# SOM_EVAL_BOARD_V101.net
KiCad netlist of a schematic drawn in EAGLE
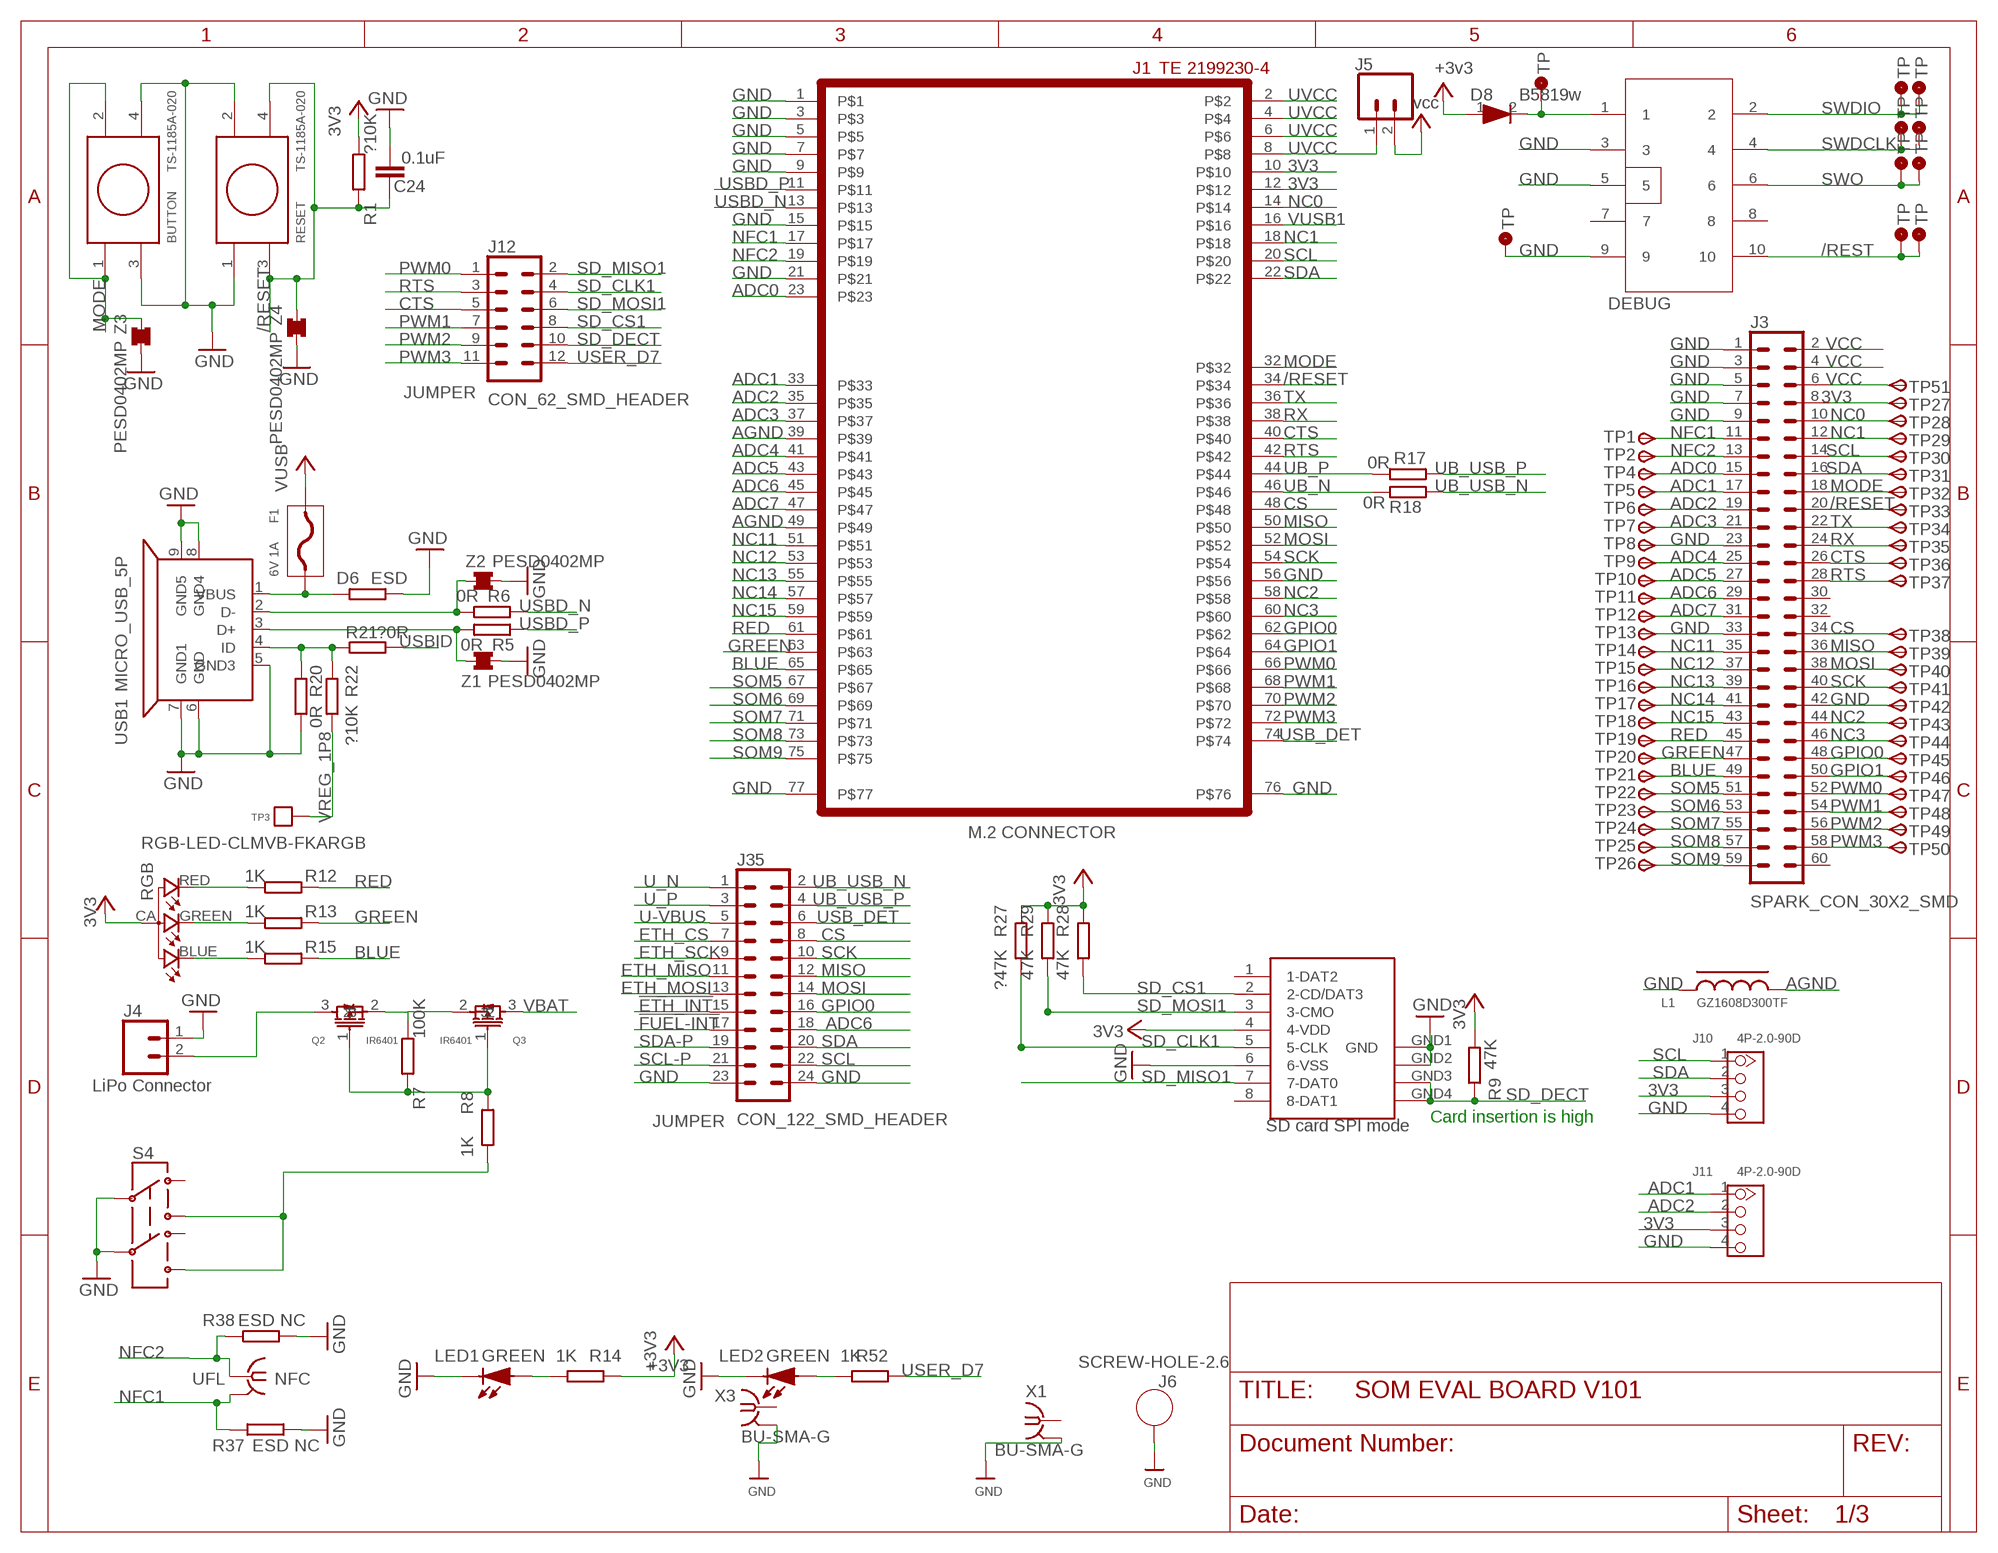
[diagram p0: schematic, sheet 1]
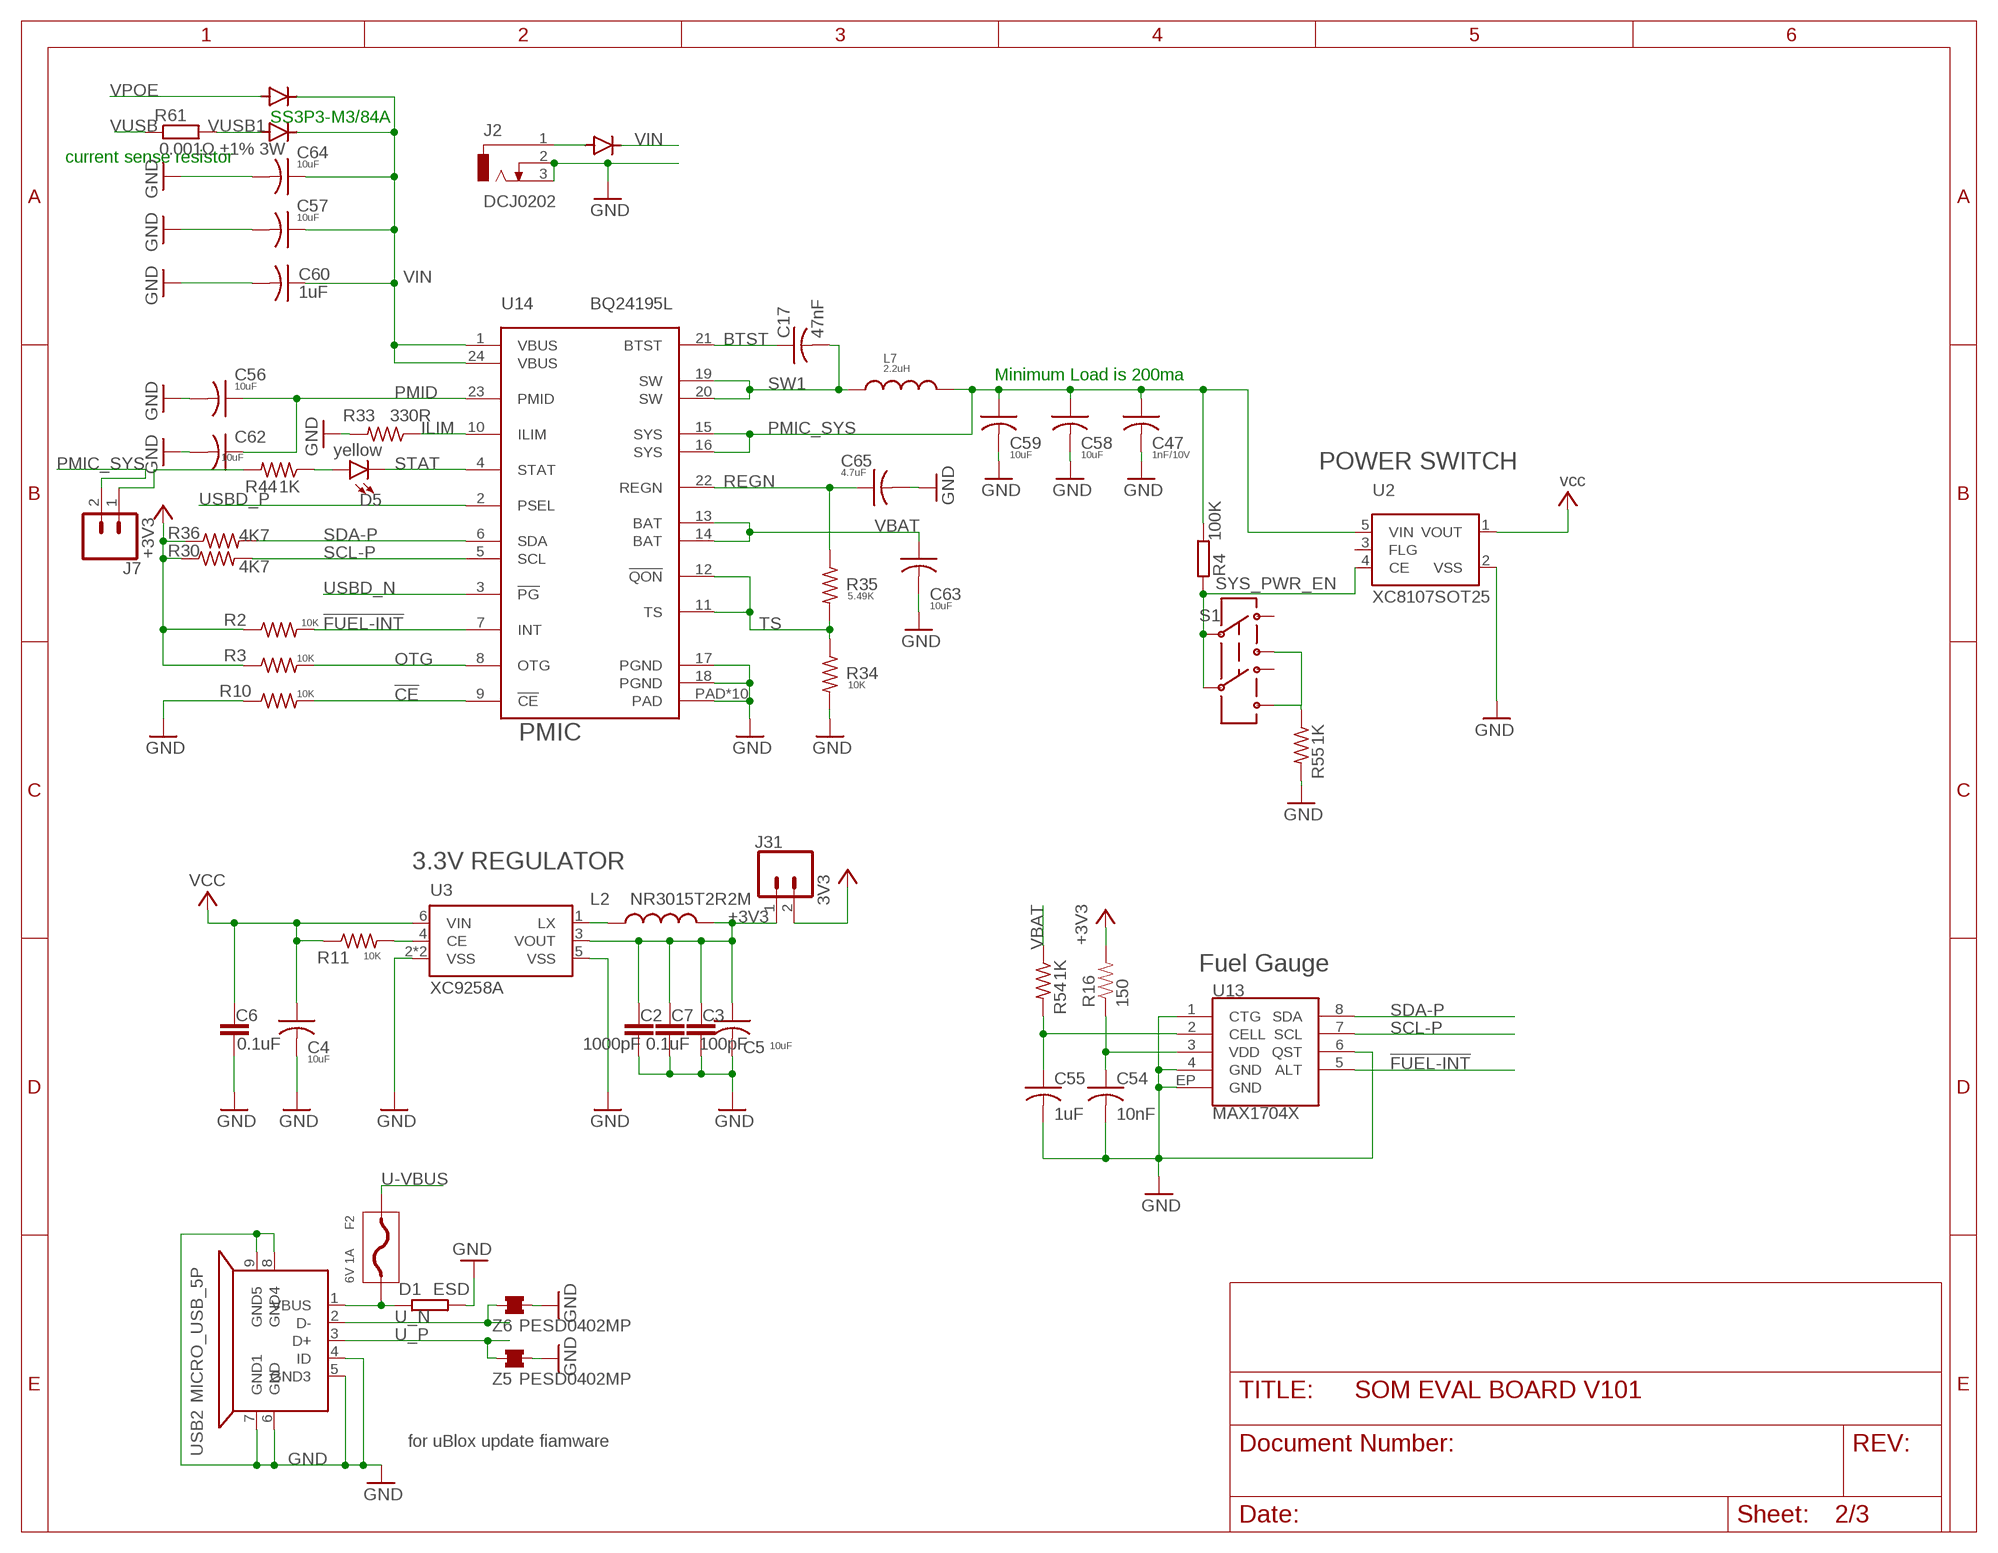
[diagram p1: schematic, sheet 2]
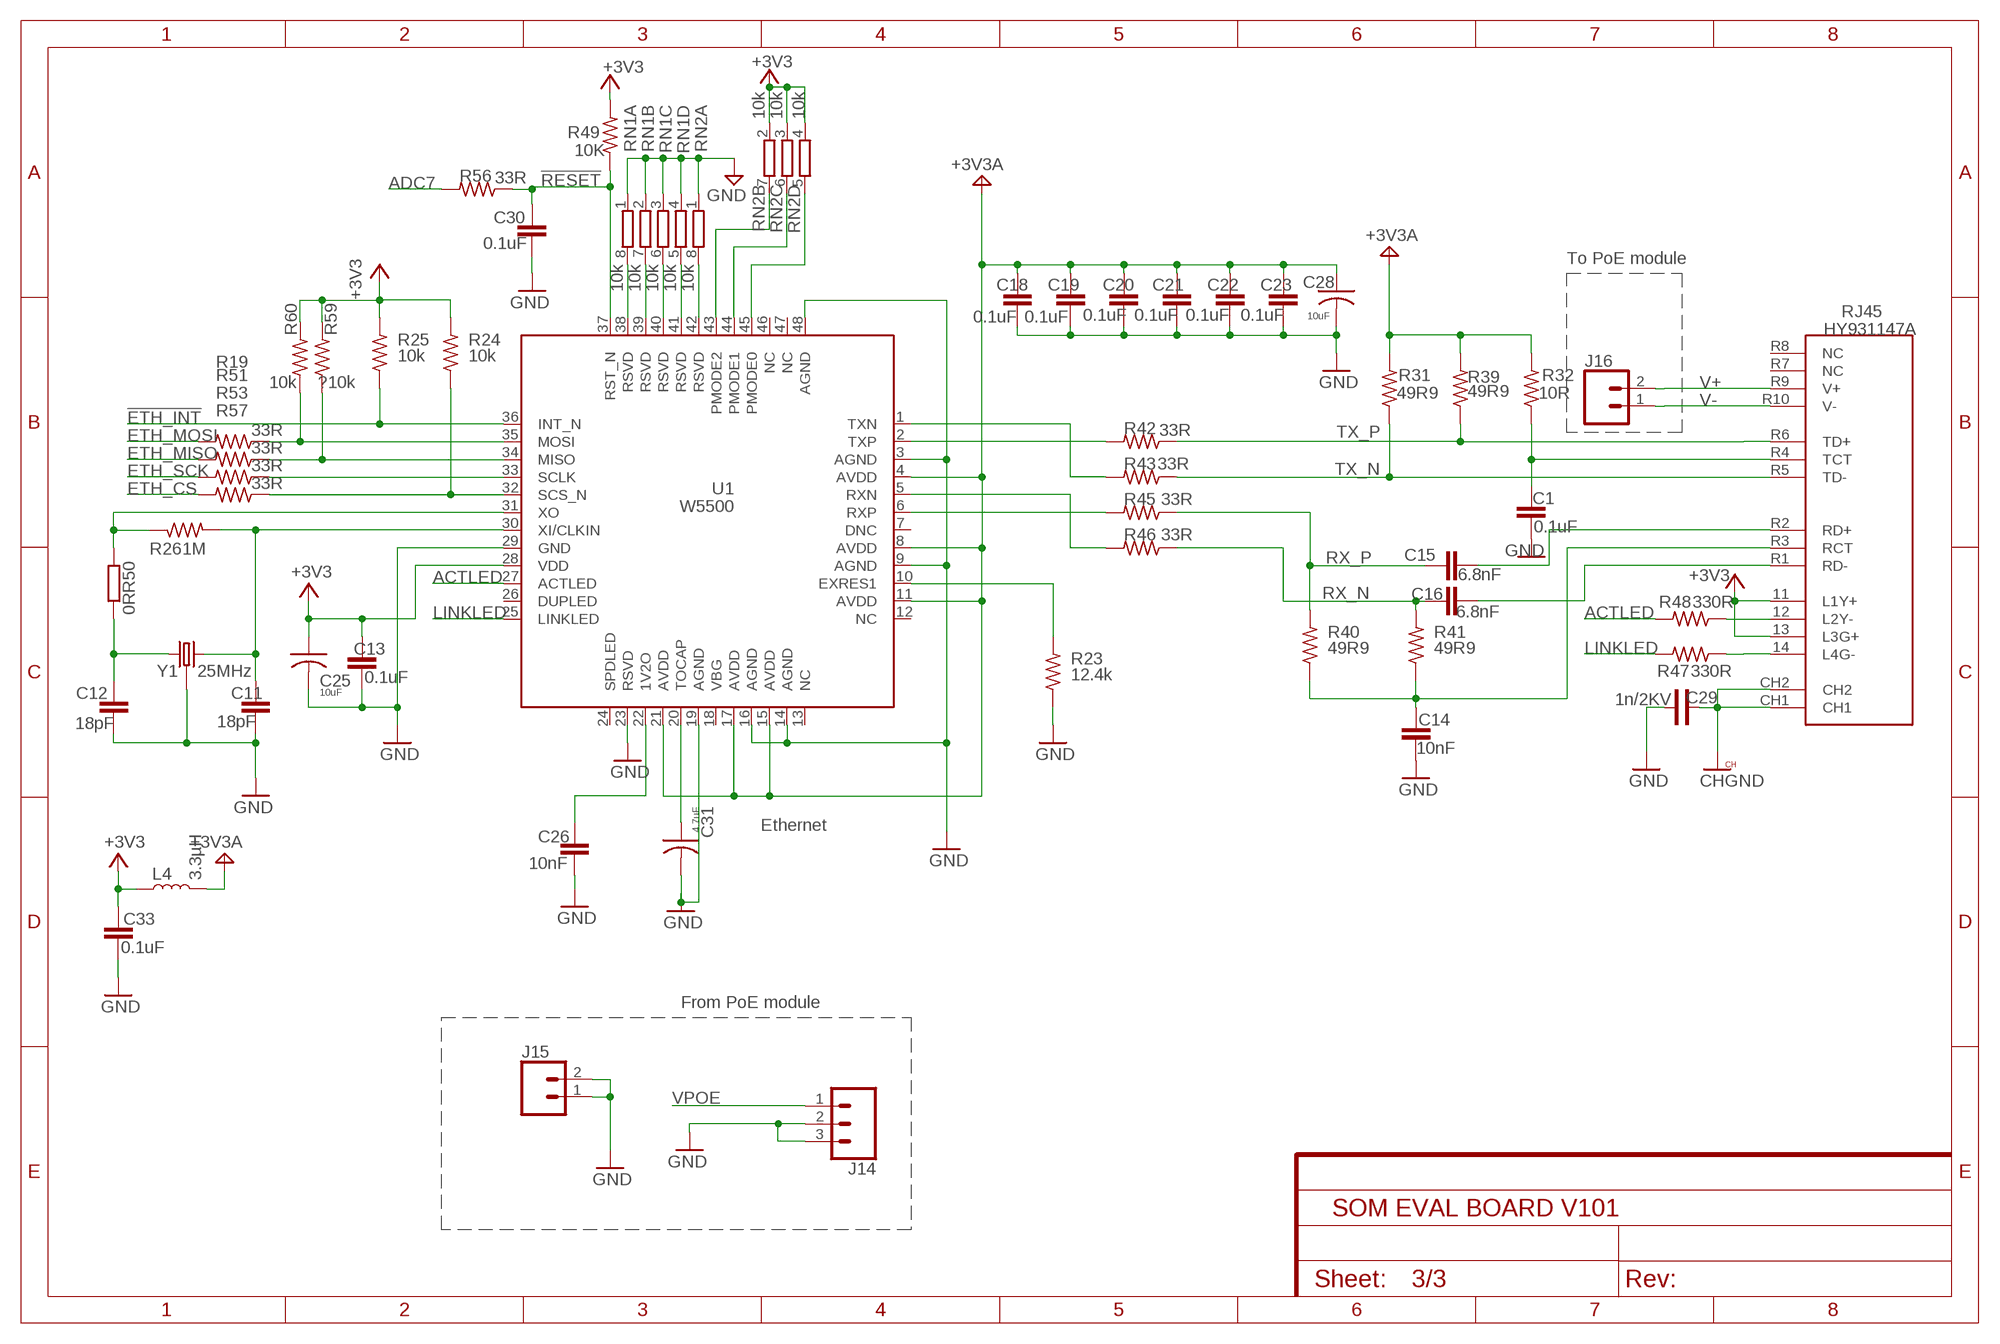
[diagram p2: schematic, sheet 3]

(export (version "E")
  (design (tool "Eeschema 10.0.6"))
  (components
    (comp (ref "BUTTON")
      (value "TS-1185A-020")
      (footprint "eagle-import:TS-1185A-020")
      (libsource (lib "eagle-import") (part "TS-1185A-020"))
    )
    (comp (ref "C24")
      (value "0.1uF")
      (footprint "eagle-import:C0402_B")
      (libsource (lib "eagle-import") (part "CAP_1"))
    )
    (comp (ref "D6")
      (value "ESD")
      (footprint "eagle-import:R-0402S")
      (libsource (lib "eagle-import") (part "RES0402S"))
    )
    (comp (ref "D8")
      (value "B5819w")
      (footprint "eagle-import:SOD-123")
      (libsource (lib "eagle-import") (part "DIODESOD123"))
    )
    (comp (ref "DEBUG")
      (value "CON5X2")
      (footprint "eagle-import:CON5X2_1.27")
      (libsource (lib "eagle-import") (part "CON5X2"))
    )
    (comp (ref "F1")
      (value "6V 1A")
      (footprint "eagle-import:F0805")
      (libsource (lib "eagle-import") (part "FUSE"))
    )
    (comp (ref "J1")
      (value "TE 2199230-4")
      (footprint "eagle-import:M.2EKEY")
      (libsource (lib "eagle-import") (part "M.2EKEY"))
    )
    (comp (ref "J3")
      (value "SPARK_CON_30X2_SMD")
      (footprint "eagle-import:SPARK_CON_30X2_SMD")
      (libsource (lib "eagle-import") (part "SPARK_CON_30X2_SMD"))
    )
    (comp (ref "J4")
      (value "CONN_02-JST-2MM-SMT")
      (footprint "eagle-import:JST-2-SMD")
      (libsource (lib "eagle-import") (part "CONN_02-JST-2MM-SMT"))
    )
    (comp (ref "J5")
      (value "CONN_02")
      (footprint "eagle-import:1X02")
      (libsource (lib "eagle-import") (part "SparkFun-Connectors_513_CONN_02"))
    )
    (comp (ref "J6")
      (value "SCREW-HOLE-2.6")
      (footprint "eagle-import:SCREW-HOLE-2.6")
      (libsource (lib "eagle-import") (part "SCREW-HOLE-2.6"))
    )
    (comp (ref "J10")
      (value "4P-2.0-90D")
      (footprint "eagle-import:HW4-2.0-90D")
      (libsource (lib "eagle-import") (part "GROVE-CONNECTOR-DIP-90D(4P-2.0)"))
    )
    (comp (ref "J11")
      (value "4P-2.0-90D")
      (footprint "eagle-import:HW4-2.0-90D")
      (libsource (lib "eagle-import") (part "GROVE-CONNECTOR-DIP-90D(4P-2.0)"))
    )
    (comp (ref "J12")
      (value "CON_62_SMD_HEADER")
      (footprint "eagle-import:CON_6_2_SMD_HEADER")
      (libsource (lib "eagle-import") (part "CON_62_SMD_HEADER"))
    )
    (comp (ref "J35")
      (value "CON_122_SMD_HEADER")
      (footprint "eagle-import:CON_12_2_SMD_HEADER")
      (libsource (lib "eagle-import") (part "CON_122_SMD_HEADER"))
    )
    (comp (ref "L1")
      (value "GZ1608D300TF")
      (footprint "eagle-import:R-0603A")
      (libsource (lib "eagle-import") (part "L"))
    )
    (comp (ref "LED1")
      (value "GREEN")
      (footprint "eagle-import:LED0603")
      (libsource (lib "eagle-import") (part "LED"))
    )
    (comp (ref "LED2")
      (value "GREEN")
      (footprint "eagle-import:LED0603")
      (libsource (lib "eagle-import") (part "LED"))
    )
    (comp (ref "NFC")
      (value "UFL")
      (footprint "eagle-import:IPEX-20279-001E")
      (libsource (lib "eagle-import") (part "IPEX-20279-001E"))
    )
    (comp (ref "P1")
      (value "SPARK_POGOPIN")
      (footprint "eagle-import:SPARK_POGO-2.0")
      (libsource (lib "eagle-import") (part "SPARK_POGOPIN"))
    )
    (comp (ref "P2")
      (value "SPARK_POGOPIN")
      (footprint "eagle-import:SPARK_POGO-2.0")
      (libsource (lib "eagle-import") (part "SPARK_POGOPIN"))
    )
    (comp (ref "P3")
      (value "SPARK_POGOPIN")
      (footprint "eagle-import:SPARK_POGO-2.0")
      (libsource (lib "eagle-import") (part "SPARK_POGOPIN"))
    )
    (comp (ref "P4")
      (value "SPARK_POGOPIN")
      (footprint "eagle-import:SPARK_POGO-2.0")
      (libsource (lib "eagle-import") (part "SPARK_POGOPIN"))
    )
    (comp (ref "Q2")
      (value "IR6401")
      (footprint "eagle-import:SOT-23")
      (libsource (lib "eagle-import") (part "PMOS"))
    )
    (comp (ref "Q3")
      (value "IR6401")
      (footprint "eagle-import:SOT-23")
      (libsource (lib "eagle-import") (part "PMOS"))
    )
    (comp (ref "R1")
      (value "?10K")
      (footprint "eagle-import:R-0402S")
      (libsource (lib "eagle-import") (part "RES0402S"))
    )
    (comp (ref "R5")
      (value "0R")
      (footprint "eagle-import:R-0402S")
      (libsource (lib "eagle-import") (part "RES0402S"))
    )
    (comp (ref "R6")
      (value "0R")
      (footprint "eagle-import:R-0402S")
      (libsource (lib "eagle-import") (part "RES0402S"))
    )
    (comp (ref "R7")
      (value "100K")
      (footprint "eagle-import:R0603")
      (libsource (lib "eagle-import") (part "RESR0603"))
    )
    (comp (ref "R8")
      (value "1K")
      (footprint "eagle-import:R-0402S")
      (libsource (lib "eagle-import") (part "RES0402S"))
    )
    (comp (ref "R9")
      (value "47K")
      (footprint "eagle-import:R-0402S")
      (libsource (lib "eagle-import") (part "RES0402S"))
    )
    (comp (ref "R12")
      (value "1K")
      (footprint "eagle-import:R-0402S")
      (libsource (lib "eagle-import") (part "RES0402S"))
    )
    (comp (ref "R13")
      (value "1K")
      (footprint "eagle-import:R-0402S")
      (libsource (lib "eagle-import") (part "RES0402S"))
    )
    (comp (ref "R14")
      (value "1K")
      (footprint "eagle-import:R-0402S")
      (libsource (lib "eagle-import") (part "RES0402S"))
    )
    (comp (ref "R15")
      (value "1K")
      (footprint "eagle-import:R-0402S")
      (libsource (lib "eagle-import") (part "RES0402S"))
    )
    (comp (ref "R17")
      (value "0R")
      (footprint "eagle-import:R-0402S")
      (libsource (lib "eagle-import") (part "RES0402S"))
    )
    (comp (ref "R18")
      (value "0R")
      (footprint "eagle-import:R-0402S")
      (libsource (lib "eagle-import") (part "RES0402S"))
    )
    (comp (ref "R20")
      (value "0R")
      (footprint "eagle-import:R-0402S")
      (libsource (lib "eagle-import") (part "RES0402S"))
    )
    (comp (ref "R21")
      (value "?0R")
      (footprint "eagle-import:R-0402S")
      (libsource (lib "eagle-import") (part "RES0402S"))
    )
    (comp (ref "R22")
      (value "?10K")
      (footprint "eagle-import:R-0402S")
      (libsource (lib "eagle-import") (part "RES0402S"))
    )
    (comp (ref "R27")
      (value "?47K")
      (footprint "eagle-import:R-0402S")
      (libsource (lib "eagle-import") (part "RES0402S"))
    )
    (comp (ref "R28")
      (value "47K")
      (footprint "eagle-import:R-0402S")
      (libsource (lib "eagle-import") (part "RES0402S"))
    )
    (comp (ref "R29")
      (value "47K")
      (footprint "eagle-import:R-0402S")
      (libsource (lib "eagle-import") (part "RES0402S"))
    )
    (comp (ref "R37")
      (value "ESD NC")
      (footprint "eagle-import:R-0402S")
      (libsource (lib "eagle-import") (part "RES0402S"))
    )
    (comp (ref "R38")
      (value "ESD NC")
      (footprint "eagle-import:R-0402S")
      (libsource (lib "eagle-import") (part "RES0402S"))
    )
    (comp (ref "R52")
      (value "1K")
      (footprint "eagle-import:R-0402S")
      (libsource (lib "eagle-import") (part "RES0402S"))
    )
    (comp (ref "RESET")
      (value "TS-1185A-020")
      (footprint "eagle-import:TS-1185A-020")
      (libsource (lib "eagle-import") (part "TS-1185A-020"))
    )
    (comp (ref "RGB")
      (value "RGB-LED-CLMVB-FKARGB")
      (footprint "eagle-import:PLCC4-2MM-RGB")
      (libsource (lib "eagle-import") (part "RGB-LED-CLMVB-FKARGB"))
    )
    (comp (ref "S4")
      (value "SWITCH-DPDT")
      (footprint "eagle-import:SWITCH-2.5X3.2-6")
      (libsource (lib "eagle-import") (part "SWITCH-DPDT"))
    )
    (comp (ref "TP1")
      (value "TPSB1,27")
      (footprint "eagle-import:B1,27")
      (libsource (lib "eagle-import") (part "TPSB1,27"))
    )
    (comp (ref "TP2")
      (value "TPSB1,27")
      (footprint "eagle-import:B1,27")
      (libsource (lib "eagle-import") (part "TPSB1,27"))
    )
    (comp (ref "TP3")
      (value "TPTP")
      (footprint "eagle-import:TP")
      (libsource (lib "eagle-import") (part "TPTP"))
    )
    (comp (ref "TP4")
      (value "TPSB1,27")
      (footprint "eagle-import:B1,27")
      (libsource (lib "eagle-import") (part "TPSB1,27"))
    )
    (comp (ref "TP5")
      (value "TPSB1,27")
      (footprint "eagle-import:B1,27")
      (libsource (lib "eagle-import") (part "TPSB1,27"))
    )
    (comp (ref "TP6")
      (value "TPSB1,27")
      (footprint "eagle-import:B1,27")
      (libsource (lib "eagle-import") (part "TPSB1,27"))
    )
    (comp (ref "TP7")
      (value "TPSB1,27")
      (footprint "eagle-import:B1,27")
      (libsource (lib "eagle-import") (part "TPSB1,27"))
    )
    (comp (ref "TP8")
      (value "TPSB1,27")
      (footprint "eagle-import:B1,27")
      (libsource (lib "eagle-import") (part "TPSB1,27"))
    )
    (comp (ref "TP9")
      (value "TPSB1,27")
      (footprint "eagle-import:B1,27")
      (libsource (lib "eagle-import") (part "TPSB1,27"))
    )
    (comp (ref "TP10")
      (value "TPSB1,27")
      (footprint "eagle-import:B1,27")
      (libsource (lib "eagle-import") (part "TPSB1,27"))
    )
    (comp (ref "TP11")
      (value "TPSB1,27")
      (footprint "eagle-import:B1,27")
      (libsource (lib "eagle-import") (part "TPSB1,27"))
    )
    (comp (ref "TP12")
      (value "TPSB1,27")
      (footprint "eagle-import:B1,27")
      (libsource (lib "eagle-import") (part "TPSB1,27"))
    )
    (comp (ref "TP13")
      (value "TPSB1,27")
      (footprint "eagle-import:B1,27")
      (libsource (lib "eagle-import") (part "TPSB1,27"))
    )
    (comp (ref "TP14")
      (value "TPSB1,27")
      (footprint "eagle-import:B1,27")
      (libsource (lib "eagle-import") (part "TPSB1,27"))
    )
    (comp (ref "TP15")
      (value "TPSB1,27")
      (footprint "eagle-import:B1,27")
      (libsource (lib "eagle-import") (part "TPSB1,27"))
    )
    (comp (ref "TP16")
      (value "TPSB1,27")
      (footprint "eagle-import:B1,27")
      (libsource (lib "eagle-import") (part "TPSB1,27"))
    )
    (comp (ref "TP17")
      (value "TPSB1,27")
      (footprint "eagle-import:B1,27")
      (libsource (lib "eagle-import") (part "TPSB1,27"))
    )
    (comp (ref "TP18")
      (value "TPSB1,27")
      (footprint "eagle-import:B1,27")
      (libsource (lib "eagle-import") (part "TPSB1,27"))
    )
    (comp (ref "TP19")
      (value "TPSB1,27")
      (footprint "eagle-import:B1,27")
      (libsource (lib "eagle-import") (part "TPSB1,27"))
    )
    (comp (ref "TP20")
      (value "TPSB1,27")
      (footprint "eagle-import:B1,27")
      (libsource (lib "eagle-import") (part "TPSB1,27"))
    )
    (comp (ref "TP21")
      (value "TPSB1,27")
      (footprint "eagle-import:B1,27")
      (libsource (lib "eagle-import") (part "TPSB1,27"))
    )
    (comp (ref "TP22")
      (value "TPSB1,27")
      (footprint "eagle-import:B1,27")
      (libsource (lib "eagle-import") (part "TPSB1,27"))
    )
    (comp (ref "TP23")
      (value "TPSB1,27")
      (footprint "eagle-import:B1,27")
      (libsource (lib "eagle-import") (part "TPSB1,27"))
    )
    (comp (ref "TP24")
      (value "TPSB1,27")
      (footprint "eagle-import:B1,27")
      (libsource (lib "eagle-import") (part "TPSB1,27"))
    )
    (comp (ref "TP25")
      (value "TPSB1,27")
      (footprint "eagle-import:B1,27")
      (libsource (lib "eagle-import") (part "TPSB1,27"))
    )
    (comp (ref "TP26")
      (value "TPSB1,27")
      (footprint "eagle-import:B1,27")
      (libsource (lib "eagle-import") (part "TPSB1,27"))
    )
    (comp (ref "TP27")
      (value "TPSB1,27")
      (footprint "eagle-import:B1,27")
      (libsource (lib "eagle-import") (part "TPSB1,27"))
    )
    (comp (ref "TP28")
      (value "TPSB1,27")
      (footprint "eagle-import:B1,27")
      (libsource (lib "eagle-import") (part "TPSB1,27"))
    )
    (comp (ref "TP29")
      (value "TPSB1,27")
      (footprint "eagle-import:B1,27")
      (libsource (lib "eagle-import") (part "TPSB1,27"))
    )
    (comp (ref "TP30")
      (value "TPSB1,27")
      (footprint "eagle-import:B1,27")
      (libsource (lib "eagle-import") (part "TPSB1,27"))
    )
    (comp (ref "TP31")
      (value "TPSB1,27")
      (footprint "eagle-import:B1,27")
      (libsource (lib "eagle-import") (part "TPSB1,27"))
    )
    (comp (ref "TP32")
      (value "TPSB1,27")
      (footprint "eagle-import:B1,27")
      (libsource (lib "eagle-import") (part "TPSB1,27"))
    )
    (comp (ref "TP33")
      (value "TPSB1,27")
      (footprint "eagle-import:B1,27")
      (libsource (lib "eagle-import") (part "TPSB1,27"))
    )
    (comp (ref "TP34")
      (value "TPSB1,27")
      (footprint "eagle-import:B1,27")
      (libsource (lib "eagle-import") (part "TPSB1,27"))
    )
    (comp (ref "TP35")
      (value "TPSB1,27")
      (footprint "eagle-import:B1,27")
      (libsource (lib "eagle-import") (part "TPSB1,27"))
    )
    (comp (ref "TP36")
      (value "TPSB1,27")
      (footprint "eagle-import:B1,27")
      (libsource (lib "eagle-import") (part "TPSB1,27"))
    )
    (comp (ref "TP37")
      (value "TPSB1,27")
      (footprint "eagle-import:B1,27")
      (libsource (lib "eagle-import") (part "TPSB1,27"))
    )
    (comp (ref "TP38")
      (value "TPSB1,27")
      (footprint "eagle-import:B1,27")
      (libsource (lib "eagle-import") (part "TPSB1,27"))
    )
    (comp (ref "TP39")
      (value "TPSB1,27")
      (footprint "eagle-import:B1,27")
      (libsource (lib "eagle-import") (part "TPSB1,27"))
    )
    (comp (ref "TP40")
      (value "TPSB1,27")
      (footprint "eagle-import:B1,27")
      (libsource (lib "eagle-import") (part "TPSB1,27"))
    )
    (comp (ref "TP41")
      (value "TPSB1,27")
      (footprint "eagle-import:B1,27")
      (libsource (lib "eagle-import") (part "TPSB1,27"))
    )
    (comp (ref "TP42")
      (value "TPSB1,27")
      (footprint "eagle-import:B1,27")
      (libsource (lib "eagle-import") (part "TPSB1,27"))
    )
    (comp (ref "TP43")
      (value "TPSB1,27")
      (footprint "eagle-import:B1,27")
      (libsource (lib "eagle-import") (part "TPSB1,27"))
    )
    (comp (ref "TP44")
      (value "TPSB1,27")
      (footprint "eagle-import:B1,27")
      (libsource (lib "eagle-import") (part "TPSB1,27"))
    )
    (comp (ref "TP45")
      (value "TPSB1,27")
      (footprint "eagle-import:B1,27")
      (libsource (lib "eagle-import") (part "TPSB1,27"))
    )
    (comp (ref "TP46")
      (value "TPSB1,27")
      (footprint "eagle-import:B1,27")
      (libsource (lib "eagle-import") (part "TPSB1,27"))
    )
    (comp (ref "TP47")
      (value "TPSB1,27")
      (footprint "eagle-import:B1,27")
      (libsource (lib "eagle-import") (part "TPSB1,27"))
    )
    (comp (ref "TP48")
      (value "TPSB1,27")
      (footprint "eagle-import:B1,27")
      (libsource (lib "eagle-import") (part "TPSB1,27"))
    )
    (comp (ref "TP49")
      (value "TPSB1,27")
      (footprint "eagle-import:B1,27")
      (libsource (lib "eagle-import") (part "TPSB1,27"))
    )
    (comp (ref "TP50")
      (value "TPSB1,27")
      (footprint "eagle-import:B1,27")
      (libsource (lib "eagle-import") (part "TPSB1,27"))
    )
    (comp (ref "TP51")
      (value "TPSB1,27")
      (footprint "eagle-import:B1,27")
      (libsource (lib "eagle-import") (part "TPSB1,27"))
    )
    (comp (ref "U$1")
      (value "TP2")
      (footprint "eagle-import:TP70_BOT")
      (libsource (lib "eagle-import") (part "TP2"))
    )
    (comp (ref "U$2")
      (value "TP2")
      (footprint "eagle-import:TP70_BOT")
      (libsource (lib "eagle-import") (part "TP2"))
    )
    (comp (ref "U$9")
      (value "TP2")
      (footprint "eagle-import:TP70_BOT")
      (libsource (lib "eagle-import") (part "TP2"))
    )
    (comp (ref "U$10")
      (value "TP2")
      (footprint "eagle-import:TP70_BOT")
      (libsource (lib "eagle-import") (part "TP2"))
    )
    (comp (ref "U$11")
      (value "TP2")
      (footprint "eagle-import:TP70_BOT")
      (libsource (lib "eagle-import") (part "TP2"))
    )
    (comp (ref "U$12")
      (value "TP2")
      (footprint "eagle-import:TP70_BOT")
      (libsource (lib "eagle-import") (part "TP2"))
    )
    (comp (ref "USB1")
      (value "MICRO_USB_5P")
      (footprint "eagle-import:MICRO_USB")
      (libsource (lib "eagle-import") (part "MICRO_USBMICRO_USB"))
    )
    (comp (ref "X1")
      (value "BU-SMA-G")
      (footprint "eagle-import:BU-SMA-G")
      (libsource (lib "eagle-import") (part "BU-SMA-G"))
    )
    (comp (ref "X3")
      (value "BU-SMA-G")
      (footprint "eagle-import:BU-SMA-G")
      (libsource (lib "eagle-import") (part "BU-SMA-G"))
    )
    (comp (ref "X4")
      (value "0046_15TW-882")
      (footprint "eagle-import:SDCARD-15TW-8821")
      (fields (field (name "PART_NUMBER") "15TW-882 REEL"))
      (libsource (lib "eagle-import") (part "0046_15TW-882"))
    )
    (comp (ref "Z1")
      (value "PESD0402MP")
      (footprint "eagle-import:SMD-0402MP")
      (libsource (lib "eagle-import") (part "PESD0402MP"))
    )
    (comp (ref "Z2")
      (value "PESD0402MP")
      (footprint "eagle-import:SMD-0402MP")
      (libsource (lib "eagle-import") (part "PESD0402MP"))
    )
    (comp (ref "Z3")
      (value "PESD0402MP")
      (footprint "eagle-import:SMD-0402MP")
      (libsource (lib "eagle-import") (part "PESD0402MP"))
    )
    (comp (ref "Z4")
      (value "PESD0402MP")
      (footprint "eagle-import:SMD-0402MP")
      (libsource (lib "eagle-import") (part "PESD0402MP"))
    )
    (comp (ref "C2")
      (value "1000pF")
      (footprint "eagle-import:C0402_B")
      (libsource (lib "eagle-import") (part "CAP_1"))
    )
    (comp (ref "C3")
      (value "100pF")
      (footprint "eagle-import:C0402_B")
      (libsource (lib "eagle-import") (part "CAP_1"))
    )
    (comp (ref "C4")
      (value "10uF")
      (footprint "eagle-import:C0603_B")
      (libsource (lib "eagle-import") (part "C-US0603"))
    )
    (comp (ref "C5")
      (value "10uF")
      (footprint "eagle-import:C0603_B")
      (libsource (lib "eagle-import") (part "C-US0603"))
    )
    (comp (ref "C6")
      (value "0.1uF")
      (footprint "eagle-import:C0402_B")
      (libsource (lib "eagle-import") (part "CAP_1"))
    )
    (comp (ref "C7")
      (value "0.1uF")
      (footprint "eagle-import:C0402_B")
      (libsource (lib "eagle-import") (part "CAP_1"))
    )
    (comp (ref "C17")
      (value "47nF")
      (footprint "eagle-import:C0201_B")
      (libsource (lib "eagle-import") (part "C-USC0201_B"))
    )
    (comp (ref "C47")
      (value "1nF/10V")
      (footprint "eagle-import:C0402_B")
      (libsource (lib "eagle-import") (part "C-US0402"))
    )
    (comp (ref "C54")
      (value "10nF")
      (footprint "eagle-import:C0402_B")
      (libsource (lib "eagle-import") (part "Spark_C-US"))
    )
    (comp (ref "C55")
      (value "1uF")
      (footprint "eagle-import:C0402_B")
      (libsource (lib "eagle-import") (part "Spark_C-US"))
    )
    (comp (ref "C56")
      (value "10uF")
      (footprint "eagle-import:C0603_B")
      (libsource (lib "eagle-import") (part "C-US0603"))
    )
    (comp (ref "C57")
      (value "10uF")
      (footprint "eagle-import:C0603_B")
      (libsource (lib "eagle-import") (part "C-US0603"))
    )
    (comp (ref "C58")
      (value "10uF")
      (footprint "eagle-import:C0603_B")
      (libsource (lib "eagle-import") (part "C-US0603"))
    )
    (comp (ref "C59")
      (value "10uF")
      (footprint "eagle-import:C0603_B")
      (libsource (lib "eagle-import") (part "C-US0603"))
    )
    (comp (ref "C60")
      (value "1uF")
      (footprint "eagle-import:C0402_B")
      (libsource (lib "eagle-import") (part "Spark_C-US"))
    )
    (comp (ref "C62")
      (value "10uF")
      (footprint "eagle-import:C0603_B")
      (libsource (lib "eagle-import") (part "C-US0603"))
    )
    (comp (ref "C63")
      (value "10uF")
      (footprint "eagle-import:C0603_B")
      (libsource (lib "eagle-import") (part "C-US0603"))
    )
    (comp (ref "C64")
      (value "10uF")
      (footprint "eagle-import:C0603_B")
      (libsource (lib "eagle-import") (part "C-US0603"))
    )
    (comp (ref "C65")
      (value "4.7uF")
      (footprint "eagle-import:C0603_B")
      (libsource (lib "eagle-import") (part "C-US0603"))
    )
    (comp (ref "D1")
      (value "ESD")
      (footprint "eagle-import:R-0402S")
      (libsource (lib "eagle-import") (part "RES0402S"))
    )
    (comp (ref "D3")
      (value "SS3P3-M3/84A")
      (footprint "eagle-import:DIODE-DO-220AA_NT(SMP)")
      (libsource (lib "eagle-import") (part "DIODE_NT"))
    )
    (comp (ref "D4")
      (value "SS3P3-M3/84A")
      (footprint "eagle-import:DIODE-DO-220AA_NT(SMP)")
      (libsource (lib "eagle-import") (part "DIODE_NT"))
    )
    (comp (ref "D5")
      (value "yellow")
      (footprint "eagle-import:LED-0603")
      (libsource (lib "eagle-import") (part "LED-RED0603"))
    )
    (comp (ref "D7")
      (value "SS3P3-M3/84A")
      (footprint "eagle-import:DIODE-DO-220AA_NT(SMP)")
      (libsource (lib "eagle-import") (part "DIODE_NT"))
    )
    (comp (ref "F2")
      (value "6V 1A")
      (footprint "eagle-import:F0805")
      (libsource (lib "eagle-import") (part "FUSE"))
    )
    (comp (ref "J2")
      (value "DCJ0202")
      (footprint "eagle-import:DCJ0202")
      (libsource (lib "eagle-import") (part "DCJ0202"))
    )
    (comp (ref "J7")
      (value "CONN_02")
      (footprint "eagle-import:1X02")
      (libsource (lib "eagle-import") (part "SparkFun-Connectors_513_CONN_02"))
    )
    (comp (ref "J31")
      (value "CONN_02")
      (footprint "eagle-import:1X02")
      (libsource (lib "eagle-import") (part "SparkFun-Connectors_513_CONN_02"))
    )
    (comp (ref "L2")
      (value "NR3015T2R2M")
      (footprint "eagle-import:INDUCTOR-VLS-E")
      (libsource (lib "eagle-import") (part "INDUCTOR-SPARKFUNVLS3012ET-4R7M"))
    )
    (comp (ref "L7")
      (value "2.2uH")
      (footprint "eagle-import:INDUCTOR-4040")
      (libsource (lib "eagle-import") (part "INDUCTORI"))
    )
    (comp (ref "R2")
      (value "10K")
      (footprint "eagle-import:R0402_B")
      (libsource (lib "eagle-import") (part "Spark_R-US_"))
    )
    (comp (ref "R3")
      (value "10K")
      (footprint "eagle-import:R0402_B")
      (libsource (lib "eagle-import") (part "Spark_R-US_"))
    )
    (comp (ref "R4")
      (value "100K")
      (footprint "eagle-import:R0603")
      (libsource (lib "eagle-import") (part "RESR0603"))
    )
    (comp (ref "R10")
      (value "10K")
      (footprint "eagle-import:R0402_B")
      (libsource (lib "eagle-import") (part "Spark_R-US_"))
    )
    (comp (ref "R11")
      (value "10K")
      (footprint "eagle-import:R0402_B")
      (libsource (lib "eagle-import") (part "Spark_R-US_"))
    )
    (comp (ref "R16")
      (value "150")
      (footprint "eagle-import:0402-RES")
      (libsource (lib "eagle-import") (part "RESISTOR0402-RES"))
    )
    (comp (ref "R30")
      (value "4K7")
      (footprint "eagle-import:C0201_B")
      (libsource (lib "eagle-import") (part "R-US_R0201_B"))
    )
    (comp (ref "R33")
      (value "330R")
      (footprint "eagle-import:R0402_B")
      (libsource (lib "eagle-import") (part "R-US_"))
    )
    (comp (ref "R34")
      (value "10K")
      (footprint "eagle-import:R0402_B")
      (libsource (lib "eagle-import") (part "Spark_R-US_"))
    )
    (comp (ref "R35")
      (value "5.49K")
      (footprint "eagle-import:R0402_B")
      (libsource (lib "eagle-import") (part "Spark_R-US_"))
    )
    (comp (ref "R36")
      (value "4K7")
      (footprint "eagle-import:C0201_B")
      (libsource (lib "eagle-import") (part "R-US_R0201_B"))
    )
    (comp (ref "R44")
      (value "1K")
      (footprint "eagle-import:R0402_B")
      (libsource (lib "eagle-import") (part "R-US_"))
    )
    (comp (ref "R54")
      (value "1K")
      (footprint "eagle-import:R0402_B")
      (libsource (lib "eagle-import") (part "R-US_"))
    )
    (comp (ref "R55")
      (value "1K")
      (footprint "eagle-import:R0402_B")
      (libsource (lib "eagle-import") (part "R-US_"))
    )
    (comp (ref "R61")
      (value "0.001Ω ±1% 3W")
      (footprint "eagle-import:R2512")
      (libsource (lib "eagle-import") (part "R-EU_R2512"))
    )
    (comp (ref "S1")
      (value "SWITCH-DPDT")
      (footprint "eagle-import:SWITCH-2.5X3.2-6")
      (libsource (lib "eagle-import") (part "SWITCH-DPDT"))
    )
    (comp (ref "U2")
      (value "XC8107SOT25")
      (footprint "eagle-import:SOT25")
      (libsource (lib "eagle-import") (part "XC8107SOT25"))
    )
    (comp (ref "U3")
      (value "XC9258A")
      (footprint "eagle-import:USP-6C")
      (libsource (lib "eagle-import") (part "XC9258A33EER-G"))
    )
    (comp (ref "U13")
      (value "MAX1704X")
      (footprint "eagle-import:TDFN-8")
      (libsource (lib "eagle-import") (part "MAX1704X"))
    )
    (comp (ref "U14")
      (value "BQ24195L")
      (footprint "eagle-import:QFN24")
      (libsource (lib "eagle-import") (part "BQ24298RTWR"))
    )
    (comp (ref "USB2")
      (value "MICRO_USB_5P")
      (footprint "eagle-import:MICRO_USB")
      (libsource (lib "eagle-import") (part "MICRO_USBMICRO_USB"))
    )
    (comp (ref "Z5")
      (value "PESD0402MP")
      (footprint "eagle-import:SMD-0402MP")
      (libsource (lib "eagle-import") (part "PESD0402MP"))
    )
    (comp (ref "Z6")
      (value "PESD0402MP")
      (footprint "eagle-import:SMD-0402MP")
      (libsource (lib "eagle-import") (part "PESD0402MP"))
    )
    (comp (ref "C1")
      (value "0.1uF")
      (footprint "eagle-import:C0402_B")
      (libsource (lib "eagle-import") (part "CAP_1"))
    )
    (comp (ref "C11")
      (value "18pF")
      (footprint "eagle-import:C0402_B")
      (libsource (lib "eagle-import") (part "CAP_1"))
    )
    (comp (ref "C12")
      (value "18pF")
      (footprint "eagle-import:C0402_B")
      (libsource (lib "eagle-import") (part "CAP_1"))
    )
    (comp (ref "C13")
      (value "0.1uF")
      (footprint "eagle-import:C0402_B")
      (libsource (lib "eagle-import") (part "CAP_1"))
    )
    (comp (ref "C14")
      (value "10nF")
      (footprint "eagle-import:C0402_B")
      (libsource (lib "eagle-import") (part "CAP_1"))
    )
    (comp (ref "C15")
      (value "6.8nF")
      (footprint "eagle-import:C0402_B")
      (libsource (lib "eagle-import") (part "CAP_1"))
    )
    (comp (ref "C16")
      (value "6.8nF")
      (footprint "eagle-import:C0402_B")
      (libsource (lib "eagle-import") (part "CAP_1"))
    )
    (comp (ref "C18")
      (value "0.1uF")
      (footprint "eagle-import:C0402_B")
      (libsource (lib "eagle-import") (part "CAP_1"))
    )
    (comp (ref "C19")
      (value "0.1uF")
      (footprint "eagle-import:C0402_B")
      (libsource (lib "eagle-import") (part "CAP_1"))
    )
    (comp (ref "C20")
      (value "0.1uF")
      (footprint "eagle-import:C0402_B")
      (libsource (lib "eagle-import") (part "CAP_1"))
    )
    (comp (ref "C21")
      (value "0.1uF")
      (footprint "eagle-import:C0402_B")
      (libsource (lib "eagle-import") (part "CAP_1"))
    )
    (comp (ref "C22")
      (value "0.1uF")
      (footprint "eagle-import:C0402_B")
      (libsource (lib "eagle-import") (part "CAP_1"))
    )
    (comp (ref "C23")
      (value "0.1uF")
      (footprint "eagle-import:C0402_B")
      (libsource (lib "eagle-import") (part "CAP_1"))
    )
    (comp (ref "C25")
      (value "10uF")
      (footprint "eagle-import:C0603_B")
      (libsource (lib "eagle-import") (part "C-US0603"))
    )
    (comp (ref "C26")
      (value "10nF")
      (footprint "eagle-import:C0402_B")
      (libsource (lib "eagle-import") (part "CAP_1"))
    )
    (comp (ref "C28")
      (value "10uF")
      (footprint "eagle-import:C0603_B")
      (libsource (lib "eagle-import") (part "C-US0603"))
    )
    (comp (ref "C29")
      (value "1n/2KV")
      (footprint "eagle-import:C-1808")
      (libsource (lib "eagle-import") (part "C-1808"))
    )
    (comp (ref "C30")
      (value "0.1uF")
      (footprint "eagle-import:C0402_B")
      (libsource (lib "eagle-import") (part "CAP_1"))
    )
    (comp (ref "C31")
      (value "4.7uF")
      (footprint "eagle-import:C0603_B")
      (libsource (lib "eagle-import") (part "C-US0603"))
    )
    (comp (ref "C33")
      (value "0.1uF")
      (footprint "eagle-import:C0402_B")
      (libsource (lib "eagle-import") (part "CAP_1"))
    )
    (comp (ref "J14")
      (value "CONN_03")
      (footprint "eagle-import:1X03")
      (libsource (lib "eagle-import") (part "CONN_03"))
    )
    (comp (ref "J15")
      (value "CONN_02")
      (footprint "eagle-import:1X02")
      (libsource (lib "eagle-import") (part "SparkFun-Connectors_513_CONN_02"))
    )
    (comp (ref "J16")
      (value "CONN_02")
      (footprint "eagle-import:1X02")
      (libsource (lib "eagle-import") (part "SparkFun-Connectors_513_CONN_02"))
    )
    (comp (ref "L4")
      (value "3.3µH")
      (footprint "eagle-import:0805")
      (libsource (lib "eagle-import") (part "INDUCTOR-0805-3.3UH"))
    )
    (comp (ref "R19")
      (value "33R")
      (footprint "eagle-import:R0402_B")
      (libsource (lib "eagle-import") (part "R-US_"))
    )
    (comp (ref "R23")
      (value "12.4k")
      (footprint "eagle-import:R0402_B")
      (libsource (lib "eagle-import") (part "R-US_"))
    )
    (comp (ref "R24")
      (value "10k")
      (footprint "eagle-import:R0402_B")
      (libsource (lib "eagle-import") (part "R-US_"))
    )
    (comp (ref "R25")
      (value "10k")
      (footprint "eagle-import:R0402_B")
      (libsource (lib "eagle-import") (part "R-US_"))
    )
    (comp (ref "R26")
      (value "1M")
      (footprint "eagle-import:R0402_B")
      (libsource (lib "eagle-import") (part "R-US_"))
    )
    (comp (ref "R31")
      (value "49R9")
      (footprint "eagle-import:R0402_B")
      (libsource (lib "eagle-import") (part "R-US_"))
    )
    (comp (ref "R32")
      (value "10R")
      (footprint "eagle-import:R0402_B")
      (libsource (lib "eagle-import") (part "R-US_"))
    )
    (comp (ref "R39")
      (value "49R9")
      (footprint "eagle-import:R0402_B")
      (libsource (lib "eagle-import") (part "R-US_"))
    )
    (comp (ref "R40")
      (value "49R9")
      (footprint "eagle-import:R0402_B")
      (libsource (lib "eagle-import") (part "R-US_"))
    )
    (comp (ref "R41")
      (value "49R9")
      (footprint "eagle-import:R0402_B")
      (libsource (lib "eagle-import") (part "R-US_"))
    )
    (comp (ref "R42")
      (value "33R")
      (footprint "eagle-import:R0402_B")
      (libsource (lib "eagle-import") (part "R-US_"))
    )
    (comp (ref "R43")
      (value "33R")
      (footprint "eagle-import:R0402_B")
      (libsource (lib "eagle-import") (part "R-US_"))
    )
    (comp (ref "R45")
      (value "33R")
      (footprint "eagle-import:R0402_B")
      (libsource (lib "eagle-import") (part "R-US_"))
    )
    (comp (ref "R46")
      (value "33R")
      (footprint "eagle-import:R0402_B")
      (libsource (lib "eagle-import") (part "R-US_"))
    )
    (comp (ref "R47")
      (value "330R")
      (footprint "eagle-import:R0402_B")
      (libsource (lib "eagle-import") (part "R-US_"))
    )
    (comp (ref "R48")
      (value "330R")
      (footprint "eagle-import:R0402_B")
      (libsource (lib "eagle-import") (part "R-US_"))
    )
    (comp (ref "R49")
      (value "10K")
      (footprint "eagle-import:R0402_B")
      (libsource (lib "eagle-import") (part "R-US_"))
    )
    (comp (ref "R50")
      (value "0R")
      (footprint "eagle-import:R-0402S")
      (libsource (lib "eagle-import") (part "RES0402S"))
    )
    (comp (ref "R51")
      (value "33R")
      (footprint "eagle-import:R0402_B")
      (libsource (lib "eagle-import") (part "R-US_"))
    )
    (comp (ref "R53")
      (value "33R")
      (footprint "eagle-import:R0402_B")
      (libsource (lib "eagle-import") (part "R-US_"))
    )
    (comp (ref "R56")
      (value "33R")
      (footprint "eagle-import:R0402_B")
      (libsource (lib "eagle-import") (part "R-US_"))
    )
    (comp (ref "R57")
      (value "33R")
      (footprint "eagle-import:R0402_B")
      (libsource (lib "eagle-import") (part "R-US_"))
    )
    (comp (ref "R59")
      (value "?10k")
      (footprint "eagle-import:R0402_B")
      (libsource (lib "eagle-import") (part "R-US_"))
    )
    (comp (ref "R60")
      (value "10k")
      (footprint "eagle-import:R0402_B")
      (libsource (lib "eagle-import") (part "R-US_"))
    )
    (comp (ref "RJ45")
      (value "HY931147A")
      (footprint "eagle-import:ARDUINO-ETHERNET-SHIELD2-V2_CONNETTORI_POE-RJ45")
      (libsource (lib "eagle-import") (part "ARDUINO-ETHERNET-SHIELD2-V2_POE_RJ45"))
    )
    (comp (ref "RN1")
      (value "10k")
      (footprint "eagle-import:4X0402ARV341")
      (libsource (lib "eagle-import") (part "4R-N0402ARV341"))
    )
    (comp (ref "RN2")
      (value "10k")
      (footprint "eagle-import:4X0402ARV341")
      (libsource (lib "eagle-import") (part "4R-N0402ARV341"))
    )
    (comp (ref "U1")
      (value "W5500")
      (footprint "eagle-import:W5500")
      (libsource (lib "eagle-import") (part "W5500"))
    )
    (comp (ref "Y1")
      (value "25MHz")
      (footprint "eagle-import:CRYSTAL-SMD-3.2X2.5MM")
      (libsource (lib "eagle-import") (part "CRYSTAL-GROUNDEDSMD-3.2X2.5"))
    )
  )
  (nets
    (net (code "1") (name "+3V3") (class "Default")
      (node (ref "C13") (pin "2") (pinfunction "P$2_2") (pintype "passive"))
      (node (ref "C2") (pin "2") (pinfunction "P$2_2") (pintype "passive"))
      (node (ref "C25") (pin "1") (pinfunction "1_1") (pintype "passive"))
      (node (ref "C3") (pin "2") (pinfunction "P$2_2") (pintype "passive"))
      (node (ref "C33") (pin "2") (pinfunction "P$2_2") (pintype "passive"))
      (node (ref "C5") (pin "1") (pinfunction "1_1") (pintype "passive"))
      (node (ref "C7") (pin "2") (pinfunction "P$2_2") (pintype "passive"))
      (node (ref "D8") (pin "1") (pinfunction "P$1_1") (pintype "bidirectional"))
      (node (ref "J31") (pin "1") (pinfunction "1_1") (pintype "passive"))
      (node (ref "L2") (pin "P$2") (pinfunction "2_P$2") (pintype "passive"))
      (node (ref "L4") (pin "1") (pinfunction "1_1") (pintype "passive"))
      (node (ref "R14") (pin "1") (pinfunction "1_1") (pintype "bidirectional"))
      (node (ref "R16") (pin "2") (pinfunction "2_2") (pintype "passive"))
      (node (ref "R2") (pin "1") (pinfunction "1_1") (pintype "passive"))
      (node (ref "R24") (pin "2") (pinfunction "2_2") (pintype "passive"))
      (node (ref "R25") (pin "2") (pinfunction "2_2") (pintype "passive"))
      (node (ref "R3") (pin "1") (pinfunction "1_1") (pintype "passive"))
      (node (ref "R30") (pin "1") (pinfunction "1_1") (pintype "passive"))
      (node (ref "R36") (pin "1") (pinfunction "1_1") (pintype "passive"))
      (node (ref "R49") (pin "2") (pinfunction "2_2") (pintype "passive"))
      (node (ref "R59") (pin "2") (pinfunction "2_2") (pintype "passive"))
      (node (ref "R60") (pin "2") (pinfunction "2_2") (pintype "passive"))
      (node (ref "RJ45") (pin "11") (pinfunction "L1Y+_11") (pintype "bidirectional"))
      (node (ref "RJ45") (pin "13") (pinfunction "L3G+_13") (pintype "bidirectional"))
      (node (ref "RN2") (pin "2") (pinfunction "1_2") (pintype "passive"))
      (node (ref "RN2") (pin "3") (pinfunction "1_3") (pintype "passive"))
      (node (ref "RN2") (pin "4") (pinfunction "1_4") (pintype "passive"))
      (node (ref "U1") (pin "28") (pinfunction "VDD_28") (pintype "passive"))
      (node (ref "U3") (pin "3") (pinfunction "VOUT_3") (pintype "power_in"))
    )
    (net (code "2") (name "+3V3A") (class "Default")
      (node (ref "C18") (pin "2") (pinfunction "P$2_2") (pintype "passive"))
      (node (ref "C19") (pin "2") (pinfunction "P$2_2") (pintype "passive"))
      (node (ref "C20") (pin "2") (pinfunction "P$2_2") (pintype "passive"))
      (node (ref "C21") (pin "2") (pinfunction "P$2_2") (pintype "passive"))
      (node (ref "C22") (pin "2") (pinfunction "P$2_2") (pintype "passive"))
      (node (ref "C23") (pin "2") (pinfunction "P$2_2") (pintype "passive"))
      (node (ref "C28") (pin "1") (pinfunction "1_1") (pintype "passive"))
      (node (ref "L4") (pin "2") (pinfunction "2_2") (pintype "passive"))
      (node (ref "R31") (pin "2") (pinfunction "2_2") (pintype "passive"))
      (node (ref "R32") (pin "2") (pinfunction "2_2") (pintype "passive"))
      (node (ref "R39") (pin "2") (pinfunction "2_2") (pintype "passive"))
      (node (ref "U1") (pin "11") (pinfunction "AVDD_11") (pintype "passive"))
      (node (ref "U1") (pin "15") (pinfunction "AVDD_15") (pintype "passive"))
      (node (ref "U1") (pin "17") (pinfunction "AVDD_17") (pintype "passive"))
      (node (ref "U1") (pin "21") (pinfunction "AVDD_21") (pintype "passive"))
      (node (ref "U1") (pin "4") (pinfunction "AVDD_4") (pintype "passive"))
      (node (ref "U1") (pin "8") (pinfunction "AVDD_8") (pintype "passive"))
    )
    (net (code "3") (name "3V3") (class "Default")
      (node (ref "J1") (pin "10") (pinfunction "P$10_10") (pintype "bidirectional"))
      (node (ref "J1") (pin "12") (pinfunction "P$12_12") (pintype "bidirectional"))
      (node (ref "J10") (pin "3") (pinfunction "3_3") (pintype "bidirectional"))
      (node (ref "J11") (pin "3") (pinfunction "3_3") (pintype "bidirectional"))
      (node (ref "J3") (pin "8") (pinfunction "8_8") (pintype "passive"))
      (node (ref "J31") (pin "2") (pinfunction "2_2") (pintype "passive"))
      (node (ref "R1") (pin "2") (pinfunction "2_2") (pintype "bidirectional"))
      (node (ref "R27") (pin "1") (pinfunction "1_1") (pintype "bidirectional"))
      (node (ref "R28") (pin "1") (pinfunction "1_1") (pintype "bidirectional"))
      (node (ref "R29") (pin "1") (pinfunction "1_1") (pintype "bidirectional"))
      (node (ref "R9") (pin "2") (pinfunction "2_2") (pintype "bidirectional"))
      (node (ref "RGB") (pin "CA") (pinfunction "1_CA") (pintype "passive"))
      (node (ref "TP27") (pin "TP") (pinfunction "PP_TP") (pintype "input"))
      (node (ref "X4") (pin "4") (pinfunction "4-VDD_4") (pintype "bidirectional"))
    )
    (net (code "4") (name "ACTLED") (class "Default")
      (node (ref "R48") (pin "2") (pinfunction "2_2") (pintype "passive"))
      (node (ref "U1") (pin "27") (pinfunction "ACTLED_27") (pintype "passive"))
    )
    (net (code "5") (name "ADC0") (class "Default")
      (node (ref "J1") (pin "23") (pinfunction "P$23_23") (pintype "bidirectional"))
      (node (ref "J3") (pin "15") (pinfunction "15_15") (pintype "passive"))
      (node (ref "TP4") (pin "TP") (pinfunction "PP_TP") (pintype "input"))
    )
    (net (code "6") (name "ADC1") (class "Default")
      (node (ref "J1") (pin "33") (pinfunction "P$33_33") (pintype "bidirectional"))
      (node (ref "J11") (pin "1") (pinfunction "1_1") (pintype "bidirectional"))
      (node (ref "J3") (pin "17") (pinfunction "17_17") (pintype "passive"))
      (node (ref "TP5") (pin "TP") (pinfunction "PP_TP") (pintype "input"))
    )
    (net (code "7") (name "ADC2") (class "Default")
      (node (ref "J1") (pin "35") (pinfunction "P$35_35") (pintype "bidirectional"))
      (node (ref "J11") (pin "2") (pinfunction "2_2") (pintype "bidirectional"))
      (node (ref "J3") (pin "19") (pinfunction "19_19") (pintype "passive"))
      (node (ref "TP6") (pin "TP") (pinfunction "PP_TP") (pintype "input"))
    )
    (net (code "8") (name "ADC3") (class "Default")
      (node (ref "J1") (pin "37") (pinfunction "P$37_37") (pintype "bidirectional"))
      (node (ref "J3") (pin "21") (pinfunction "21_21") (pintype "passive"))
      (node (ref "TP7") (pin "TP") (pinfunction "PP_TP") (pintype "input"))
    )
    (net (code "9") (name "ADC4") (class "Default")
      (node (ref "J1") (pin "41") (pinfunction "P$41_41") (pintype "bidirectional"))
      (node (ref "J3") (pin "25") (pinfunction "25_25") (pintype "passive"))
      (node (ref "TP9") (pin "TP") (pinfunction "PP_TP") (pintype "input"))
    )
    (net (code "10") (name "ADC5") (class "Default")
      (node (ref "J1") (pin "43") (pinfunction "P$43_43") (pintype "bidirectional"))
      (node (ref "J3") (pin "27") (pinfunction "27_27") (pintype "passive"))
      (node (ref "TP10") (pin "TP") (pinfunction "PP_TP") (pintype "input"))
    )
    (net (code "11") (name "ADC6") (class "Default")
      (node (ref "J1") (pin "45") (pinfunction "P$45_45") (pintype "bidirectional"))
      (node (ref "J3") (pin "29") (pinfunction "29_29") (pintype "passive"))
      (node (ref "J35") (pin "18") (pinfunction "18_18") (pintype "passive"))
      (node (ref "TP11") (pin "TP") (pinfunction "PP_TP") (pintype "input"))
    )
    (net (code "12") (name "ADC7") (class "Default")
      (node (ref "J1") (pin "47") (pinfunction "P$47_47") (pintype "bidirectional"))
      (node (ref "J3") (pin "31") (pinfunction "31_31") (pintype "passive"))
      (node (ref "R56") (pin "2") (pinfunction "2_2") (pintype "passive"))
      (node (ref "TP12") (pin "TP") (pinfunction "PP_TP") (pintype "input"))
    )
    (net (code "13") (name "AGND") (class "Default")
      (node (ref "J1") (pin "39") (pinfunction "P$39_39") (pintype "bidirectional"))
      (node (ref "J1") (pin "49") (pinfunction "P$49_49") (pintype "bidirectional"))
      (node (ref "L1") (pin "2") (pinfunction "2_2") (pintype "bidirectional"))
    )
    (net (code "14") (name "BLUE") (class "Default")
      (node (ref "J1") (pin "65") (pinfunction "P$65_65") (pintype "bidirectional"))
      (node (ref "J3") (pin "49") (pinfunction "49_49") (pintype "passive"))
      (node (ref "R15") (pin "1") (pinfunction "1_1") (pintype "bidirectional"))
      (node (ref "TP21") (pin "TP") (pinfunction "PP_TP") (pintype "input"))
    )
    (net (code "15") (name "BTST") (class "Default")
      (node (ref "C17") (pin "1") (pinfunction "1_1") (pintype "passive"))
      (node (ref "U14") (pin "21") (pinfunction "BTST_21") (pintype "bidirectional"))
    )
    (net (code "16") (name "CHGND") (class "Default")
      (node (ref "C29") (pin "P$1") (pinfunction "P$1_P$1") (pintype "passive"))
      (node (ref "RJ45") (pin "CH1") (pinfunction "CH1_CH1") (pintype "bidirectional"))
      (node (ref "RJ45") (pin "CH2") (pinfunction "CH2_CH2") (pintype "bidirectional"))
    )
    (net (code "17") (name "CS") (class "Default")
      (node (ref "J1") (pin "48") (pinfunction "P$48_48") (pintype "bidirectional"))
      (node (ref "J3") (pin "34") (pinfunction "34_34") (pintype "passive"))
      (node (ref "J35") (pin "8") (pinfunction "8_8") (pintype "passive"))
      (node (ref "TP38") (pin "TP") (pinfunction "PP_TP") (pintype "input"))
    )
    (net (code "18") (name "CTS") (class "Default")
      (node (ref "J1") (pin "40") (pinfunction "P$40_40") (pintype "bidirectional"))
      (node (ref "J12") (pin "5") (pinfunction "5_5") (pintype "passive"))
      (node (ref "J3") (pin "26") (pinfunction "26_26") (pintype "passive"))
      (node (ref "TP36") (pin "TP") (pinfunction "PP_TP") (pintype "input"))
    )
    (net (code "19") (name "ETH_CS") (class "Default")
      (node (ref "J35") (pin "7") (pinfunction "7_7") (pintype "passive"))
      (node (ref "R57") (pin "2") (pinfunction "2_2") (pintype "passive"))
    )
    (net (code "20") (name "ETH_MISO") (class "Default")
      (node (ref "J35") (pin "11") (pinfunction "11_11") (pintype "passive"))
      (node (ref "R51") (pin "2") (pinfunction "2_2") (pintype "passive"))
    )
    (net (code "21") (name "ETH_MOSI") (class "Default")
      (node (ref "J35") (pin "13") (pinfunction "13_13") (pintype "passive"))
      (node (ref "R19") (pin "2") (pinfunction "2_2") (pintype "passive"))
    )
    (net (code "22") (name "ETH_SCK") (class "Default")
      (node (ref "J35") (pin "9") (pinfunction "9_9") (pintype "passive"))
      (node (ref "R53") (pin "2") (pinfunction "2_2") (pintype "passive"))
    )
    (net (code "23") (name "GND") (class "Default")
      (node (ref "BUTTON") (pin "3") (pinfunction "P$3_3") (pintype "bidirectional"))
      (node (ref "BUTTON") (pin "4") (pinfunction "P$4_4") (pintype "bidirectional"))
      (node (ref "C1") (pin "1") (pinfunction "P$1_1") (pintype "passive"))
      (node (ref "C11") (pin "1") (pinfunction "P$1_1") (pintype "passive"))
      (node (ref "C12") (pin "1") (pinfunction "P$1_1") (pintype "passive"))
      (node (ref "C13") (pin "1") (pinfunction "P$1_1") (pintype "passive"))
      (node (ref "C14") (pin "1") (pinfunction "P$1_1") (pintype "passive"))
      (node (ref "C18") (pin "1") (pinfunction "P$1_1") (pintype "passive"))
      (node (ref "C19") (pin "1") (pinfunction "P$1_1") (pintype "passive"))
      (node (ref "C2") (pin "1") (pinfunction "P$1_1") (pintype "passive"))
      (node (ref "C20") (pin "1") (pinfunction "P$1_1") (pintype "passive"))
      (node (ref "C21") (pin "1") (pinfunction "P$1_1") (pintype "passive"))
      (node (ref "C22") (pin "1") (pinfunction "P$1_1") (pintype "passive"))
      (node (ref "C23") (pin "1") (pinfunction "P$1_1") (pintype "passive"))
      (node (ref "C24") (pin "1") (pinfunction "P$1_1") (pintype "passive"))
      (node (ref "C25") (pin "2") (pinfunction "2_2") (pintype "passive"))
      (node (ref "C26") (pin "1") (pinfunction "P$1_1") (pintype "passive"))
      (node (ref "C28") (pin "2") (pinfunction "2_2") (pintype "passive"))
      (node (ref "C29") (pin "P$2") (pinfunction "P$2_P$2") (pintype "passive"))
      (node (ref "C3") (pin "1") (pinfunction "P$1_1") (pintype "passive"))
      (node (ref "C30") (pin "1") (pinfunction "P$1_1") (pintype "passive"))
      (node (ref "C31") (pin "2") (pinfunction "2_2") (pintype "passive"))
      (node (ref "C33") (pin "1") (pinfunction "P$1_1") (pintype "passive"))
      (node (ref "C4") (pin "2") (pinfunction "2_2") (pintype "passive"))
      (node (ref "C47") (pin "2") (pinfunction "2_2") (pintype "passive"))
      (node (ref "C5") (pin "2") (pinfunction "2_2") (pintype "passive"))
      (node (ref "C54") (pin "2") (pinfunction "2_2") (pintype "passive"))
      (node (ref "C55") (pin "2") (pinfunction "2_2") (pintype "passive"))
      (node (ref "C56") (pin "2") (pinfunction "2_2") (pintype "passive"))
      (node (ref "C57") (pin "2") (pinfunction "2_2") (pintype "passive"))
      (node (ref "C58") (pin "2") (pinfunction "2_2") (pintype "passive"))
      (node (ref "C59") (pin "2") (pinfunction "2_2") (pintype "passive"))
      (node (ref "C6") (pin "1") (pinfunction "P$1_1") (pintype "passive"))
      (node (ref "C60") (pin "2") (pinfunction "2_2") (pintype "passive"))
      (node (ref "C62") (pin "2") (pinfunction "2_2") (pintype "passive"))
      (node (ref "C63") (pin "2") (pinfunction "2_2") (pintype "passive"))
      (node (ref "C64") (pin "2") (pinfunction "2_2") (pintype "passive"))
      (node (ref "C65") (pin "2") (pinfunction "2_2") (pintype "passive"))
      (node (ref "C7") (pin "1") (pinfunction "P$1_1") (pintype "passive"))
      (node (ref "D1") (pin "1") (pinfunction "1_1") (pintype "bidirectional"))
      (node (ref "D6") (pin "1") (pinfunction "1_1") (pintype "bidirectional"))
      (node (ref "DEBUG") (pin "3") (pinfunction "3_3") (pintype "bidirectional"))
      (node (ref "DEBUG") (pin "5") (pinfunction "5_5") (pintype "bidirectional"))
      (node (ref "DEBUG") (pin "9") (pinfunction "9_9") (pintype "bidirectional"))
      (node (ref "J1") (pin "1") (pinfunction "P$1_1") (pintype "bidirectional"))
      (node (ref "J1") (pin "15") (pinfunction "P$15_15") (pintype "bidirectional"))
      (node (ref "J1") (pin "21") (pinfunction "P$21_21") (pintype "bidirectional"))
      (node (ref "J1") (pin "3") (pinfunction "P$3_3") (pintype "bidirectional"))
      (node (ref "J1") (pin "5") (pinfunction "P$5_5") (pintype "bidirectional"))
      (node (ref "J1") (pin "56") (pinfunction "P$56_56") (pintype "bidirectional"))
      (node (ref "J1") (pin "7") (pinfunction "P$7_7") (pintype "bidirectional"))
      (node (ref "J1") (pin "76") (pinfunction "P$76_76") (pintype "power_in"))
      (node (ref "J1") (pin "77") (pinfunction "P$77_77") (pintype "power_in"))
      (node (ref "J1") (pin "9") (pinfunction "P$9_9") (pintype "bidirectional"))
      (node (ref "J10") (pin "4") (pinfunction "4_4") (pintype "bidirectional"))
      (node (ref "J11") (pin "4") (pinfunction "4_4") (pintype "bidirectional"))
      (node (ref "J14") (pin "2") (pinfunction "2_2") (pintype "passive"))
      (node (ref "J14") (pin "3") (pinfunction "3_3") (pintype "passive"))
      (node (ref "J15") (pin "1") (pinfunction "1_1") (pintype "passive"))
      (node (ref "J15") (pin "2") (pinfunction "2_2") (pintype "passive"))
      (node (ref "J2") (pin "2") (pinfunction "2_2") (pintype "passive"))
      (node (ref "J2") (pin "3") (pinfunction "3_3") (pintype "passive"))
      (node (ref "J3") (pin "1") (pinfunction "1_1") (pintype "passive"))
      (node (ref "J3") (pin "23") (pinfunction "23_23") (pintype "passive"))
      (node (ref "J3") (pin "3") (pinfunction "3_3") (pintype "passive"))
      (node (ref "J3") (pin "33") (pinfunction "33_33") (pintype "passive"))
      (node (ref "J3") (pin "42") (pinfunction "42_42") (pintype "passive"))
      (node (ref "J3") (pin "5") (pinfunction "5_5") (pintype "passive"))
      (node (ref "J3") (pin "7") (pinfunction "7_7") (pintype "passive"))
      (node (ref "J3") (pin "9") (pinfunction "9_9") (pintype "passive"))
      (node (ref "J35") (pin "23") (pinfunction "23_23") (pintype "passive"))
      (node (ref "J35") (pin "24") (pinfunction "24_24") (pintype "passive"))
      (node (ref "J4") (pin "1") (pinfunction "2_1") (pintype "passive"))
      (node (ref "J6") (pin "P$1") (pinfunction "GND_P$1") (pintype "bidirectional"))
      (node (ref "L1") (pin "1") (pinfunction "1_1") (pintype "bidirectional"))
      (node (ref "LED1") (pin "2") (pinfunction "K_2") (pintype "bidirectional"))
      (node (ref "LED2") (pin "2") (pinfunction "K_2") (pintype "bidirectional"))
      (node (ref "R10") (pin "1") (pinfunction "1_1") (pintype "passive"))
      (node (ref "R20") (pin "2") (pinfunction "2_2") (pintype "bidirectional"))
      (node (ref "R23") (pin "1") (pinfunction "1_1") (pintype "passive"))
      (node (ref "R33") (pin "2") (pinfunction "2_2") (pintype "passive"))
      (node (ref "R34") (pin "2") (pinfunction "2_2") (pintype "passive"))
      (node (ref "R37") (pin "2") (pinfunction "2_2") (pintype "bidirectional"))
      (node (ref "R38") (pin "1") (pinfunction "1_1") (pintype "bidirectional"))
      (node (ref "R55") (pin "2") (pinfunction "2_2") (pintype "passive"))
      (node (ref "RESET") (pin "1") (pinfunction "P$1_1") (pintype "bidirectional"))
      (node (ref "RESET") (pin "2") (pinfunction "P$2_2") (pintype "bidirectional"))
      (node (ref "RN1") (pin "1") (pinfunction "1_1") (pintype "passive"))
      (node (ref "RN1") (pin "2") (pinfunction "1_2") (pintype "passive"))
      (node (ref "RN1") (pin "3") (pinfunction "1_3") (pintype "passive"))
      (node (ref "RN1") (pin "4") (pinfunction "1_4") (pintype "passive"))
      (node (ref "RN2") (pin "1") (pinfunction "1_1") (pintype "passive"))
      (node (ref "S4") (pin "2") (pinfunction "2_2") (pintype "bidirectional"))
      (node (ref "S4") (pin "5") (pinfunction "5_5") (pintype "bidirectional"))
      (node (ref "TP13") (pin "TP") (pinfunction "PP_TP") (pintype "input"))
      (node (ref "TP42") (pin "TP") (pinfunction "PP_TP") (pintype "input"))
      (node (ref "TP8") (pin "TP") (pinfunction "PP_TP") (pintype "input"))
      (node (ref "U$2") (pin "P$1") (pinfunction "TP_P$1") (pintype "bidirectional"))
      (node (ref "U1") (pin "14") (pinfunction "AGND_14") (pintype "passive"))
      (node (ref "U1") (pin "16") (pinfunction "AGND_16") (pintype "passive"))
      (node (ref "U1") (pin "19") (pinfunction "AGND_19") (pintype "passive"))
      (node (ref "U1") (pin "23") (pinfunction "RSVD_23") (pintype "passive"))
      (node (ref "U1") (pin "29") (pinfunction "GND_29") (pintype "passive"))
      (node (ref "U1") (pin "3") (pinfunction "AGND_3") (pintype "passive"))
      (node (ref "U1") (pin "48") (pinfunction "AGND_48") (pintype "passive"))
      (node (ref "U1") (pin "9") (pinfunction "AGND_9") (pintype "passive"))
      (node (ref "U13") (pin "1") (pinfunction "CTG_1") (pintype "bidirectional"))
      (node (ref "U13") (pin "4") (pinfunction "GND_4") (pintype "bidirectional"))
      (node (ref "U13") (pin "6") (pinfunction "QST_6") (pintype "bidirectional"))
      (node (ref "U13") (pin "EP") (pinfunction "GND_EP") (pintype "bidirectional"))
      (node (ref "U14") (pin "17") (pinfunction "PGND_17") (pintype "passive"))
      (node (ref "U14") (pin "18") (pinfunction "PGND_18") (pintype "passive"))
      (node (ref "U14") (pin "PAD") (pinfunction "PAD_PAD") (pintype "power_in"))
      (node (ref "U14") (pin "PAD@1") (pinfunction "PAD_PAD@1") (pintype "power_in"))
      (node (ref "U14") (pin "PAD@2") (pinfunction "PAD_PAD@2") (pintype "power_in"))
      (node (ref "U14") (pin "PAD@3") (pinfunction "PAD_PAD@3") (pintype "power_in"))
      (node (ref "U14") (pin "PAD@4") (pinfunction "PAD_PAD@4") (pintype "power_in"))
      (node (ref "U14") (pin "PAD@5") (pinfunction "PAD_PAD@5") (pintype "power_in"))
      (node (ref "U14") (pin "PAD@6") (pinfunction "PAD_PAD@6") (pintype "power_in"))
      (node (ref "U14") (pin "PAD@7") (pinfunction "PAD_PAD@7") (pintype "power_in"))
      (node (ref "U14") (pin "PAD@8") (pinfunction "PAD_PAD@8") (pintype "power_in"))
      (node (ref "U14") (pin "PAD@9") (pinfunction "PAD_PAD@9") (pintype "power_in"))
      (node (ref "U2") (pin "2") (pinfunction "VSS_2") (pintype "power_in"))
      (node (ref "U3") (pin "2") (pinfunction "VSS_2") (pintype "power_in"))
      (node (ref "U3") (pin "5") (pinfunction "VSS_5") (pintype "power_in"))
      (node (ref "U3") (pin "P$1") (pinfunction "VSS_P$1") (pintype "power_in"))
      (node (ref "USB1") (pin "5") (pinfunction "GND3_5") (pintype "bidirectional"))
      (node (ref "USB1") (pin "6") (pinfunction "GND_6") (pintype "bidirectional"))
      (node (ref "USB1") (pin "7") (pinfunction "GND1_7") (pintype "bidirectional"))
      (node (ref "USB1") (pin "8") (pinfunction "GND4_8") (pintype "bidirectional"))
      (node (ref "USB1") (pin "9") (pinfunction "GND5_9") (pintype "bidirectional"))
      (node (ref "USB2") (pin "4") (pinfunction "ID_4") (pintype "bidirectional"))
      (node (ref "USB2") (pin "5") (pinfunction "GND3_5") (pintype "bidirectional"))
      (node (ref "USB2") (pin "6") (pinfunction "GND_6") (pintype "bidirectional"))
      (node (ref "USB2") (pin "7") (pinfunction "GND1_7") (pintype "bidirectional"))
      (node (ref "USB2") (pin "8") (pinfunction "GND4_8") (pintype "bidirectional"))
      (node (ref "USB2") (pin "9") (pinfunction "GND5_9") (pintype "bidirectional"))
      (node (ref "X1") (pin "2") (pinfunction "2_2") (pintype "passive"))
      (node (ref "X1") (pin "3") (pinfunction "2_3") (pintype "passive"))
      (node (ref "X1") (pin "4") (pinfunction "2_4") (pintype "passive"))
      (node (ref "X1") (pin "5") (pinfunction "2_5") (pintype "passive"))
      (node (ref "X3") (pin "2") (pinfunction "2_2") (pintype "passive"))
      (node (ref "X3") (pin "3") (pinfunction "2_3") (pintype "passive"))
      (node (ref "X3") (pin "4") (pinfunction "2_4") (pintype "passive"))
      (node (ref "X3") (pin "5") (pinfunction "2_5") (pintype "passive"))
      (node (ref "X4") (pin "6") (pinfunction "6-VSS_6") (pintype "bidirectional"))
      (node (ref "X4") (pin "GND1") (pinfunction "GND_GND1") (pintype "power_in"))
      (node (ref "X4") (pin "GND2") (pinfunction "GND1_GND2") (pintype "power_in"))
      (node (ref "Y1") (pin "2") (pinfunction "3_2") (pintype "passive"))
      (node (ref "Y1") (pin "4") (pinfunction "3_4") (pintype "passive"))
      (node (ref "Z1") (pin "1") (pinfunction "1_1") (pintype "passive"))
      (node (ref "Z2") (pin "1") (pinfunction "1_1") (pintype "passive"))
      (node (ref "Z3") (pin "1") (pinfunction "1_1") (pintype "passive"))
      (node (ref "Z4") (pin "1") (pinfunction "1_1") (pintype "passive"))
      (node (ref "Z5") (pin "1") (pinfunction "1_1") (pintype "passive"))
      (node (ref "Z6") (pin "1") (pinfunction "1_1") (pintype "passive"))
    )
    (net (code "24") (name "GPIO0") (class "Default")
      (node (ref "J1") (pin "62") (pinfunction "P$62_62") (pintype "bidirectional"))
      (node (ref "J3") (pin "48") (pinfunction "48_48") (pintype "passive"))
      (node (ref "J35") (pin "16") (pinfunction "16_16") (pintype "passive"))
      (node (ref "TP45") (pin "TP") (pinfunction "PP_TP") (pintype "input"))
    )
    (net (code "25") (name "GPIO1") (class "Default")
      (node (ref "J1") (pin "64") (pinfunction "P$64_64") (pintype "bidirectional"))
      (node (ref "J3") (pin "50") (pinfunction "50_50") (pintype "passive"))
      (node (ref "TP46") (pin "TP") (pinfunction "PP_TP") (pintype "input"))
    )
    (net (code "26") (name "GREEN") (class "Default")
      (node (ref "J1") (pin "63") (pinfunction "P$63_63") (pintype "bidirectional"))
      (node (ref "J3") (pin "47") (pinfunction "47_47") (pintype "passive"))
      (node (ref "R13") (pin "1") (pinfunction "1_1") (pintype "bidirectional"))
      (node (ref "TP20") (pin "TP") (pinfunction "PP_TP") (pintype "input"))
    )
    (net (code "27") (name "ILIM") (class "Default")
      (node (ref "R33") (pin "1") (pinfunction "1_1") (pintype "passive"))
      (node (ref "U14") (pin "10") (pinfunction "ILIM_10") (pintype "output"))
    )
    (net (code "28") (name "LINKLED") (class "Default")
      (node (ref "R47") (pin "2") (pinfunction "2_2") (pintype "passive"))
      (node (ref "U1") (pin "25") (pinfunction "LINKLED_25") (pintype "passive"))
    )
    (net (code "29") (name "MISO") (class "Default")
      (node (ref "J1") (pin "50") (pinfunction "P$50_50") (pintype "bidirectional"))
      (node (ref "J3") (pin "36") (pinfunction "36_36") (pintype "passive"))
      (node (ref "J35") (pin "12") (pinfunction "12_12") (pintype "passive"))
      (node (ref "TP39") (pin "TP") (pinfunction "PP_TP") (pintype "input"))
    )
    (net (code "30") (name "MODE") (class "Default")
      (node (ref "BUTTON") (pin "1") (pinfunction "P$1_1") (pintype "bidirectional"))
      (node (ref "BUTTON") (pin "2") (pinfunction "P$2_2") (pintype "bidirectional"))
      (node (ref "J1") (pin "32") (pinfunction "P$32_32") (pintype "bidirectional"))
      (node (ref "J3") (pin "18") (pinfunction "18_18") (pintype "passive"))
      (node (ref "TP32") (pin "TP") (pinfunction "PP_TP") (pintype "input"))
      (node (ref "Z3") (pin "2") (pinfunction "2_2") (pintype "passive"))
    )
    (net (code "31") (name "MOSI") (class "Default")
      (node (ref "J1") (pin "52") (pinfunction "P$52_52") (pintype "bidirectional"))
      (node (ref "J3") (pin "38") (pinfunction "38_38") (pintype "passive"))
      (node (ref "J35") (pin "14") (pinfunction "14_14") (pintype "passive"))
      (node (ref "TP40") (pin "TP") (pinfunction "PP_TP") (pintype "input"))
    )
    (net (code "32") (name "NC0") (class "Default")
      (node (ref "J1") (pin "14") (pinfunction "P$14_14") (pintype "bidirectional"))
      (node (ref "J3") (pin "10") (pinfunction "10_10") (pintype "passive"))
      (node (ref "TP28") (pin "TP") (pinfunction "PP_TP") (pintype "input"))
    )
    (net (code "33") (name "NC1") (class "Default")
      (node (ref "J1") (pin "18") (pinfunction "P$18_18") (pintype "bidirectional"))
      (node (ref "J3") (pin "12") (pinfunction "12_12") (pintype "passive"))
      (node (ref "TP29") (pin "TP") (pinfunction "PP_TP") (pintype "input"))
    )
    (net (code "34") (name "NC2") (class "Default")
      (node (ref "J1") (pin "58") (pinfunction "P$58_58") (pintype "bidirectional"))
      (node (ref "J3") (pin "44") (pinfunction "44_44") (pintype "passive"))
      (node (ref "TP43") (pin "TP") (pinfunction "PP_TP") (pintype "input"))
    )
    (net (code "35") (name "NC3") (class "Default")
      (node (ref "J1") (pin "60") (pinfunction "P$60_60") (pintype "bidirectional"))
      (node (ref "J3") (pin "46") (pinfunction "46_46") (pintype "passive"))
      (node (ref "TP44") (pin "TP") (pinfunction "PP_TP") (pintype "input"))
    )
    (net (code "36") (name "NC11") (class "Default")
      (node (ref "J1") (pin "51") (pinfunction "P$51_51") (pintype "bidirectional"))
      (node (ref "J3") (pin "35") (pinfunction "35_35") (pintype "passive"))
      (node (ref "TP14") (pin "TP") (pinfunction "PP_TP") (pintype "input"))
    )
    (net (code "37") (name "NC12") (class "Default")
      (node (ref "J1") (pin "53") (pinfunction "P$53_53") (pintype "bidirectional"))
      (node (ref "J3") (pin "37") (pinfunction "37_37") (pintype "passive"))
      (node (ref "TP15") (pin "TP") (pinfunction "PP_TP") (pintype "input"))
    )
    (net (code "38") (name "NC13") (class "Default")
      (node (ref "J1") (pin "55") (pinfunction "P$55_55") (pintype "bidirectional"))
      (node (ref "J3") (pin "39") (pinfunction "39_39") (pintype "passive"))
      (node (ref "TP16") (pin "TP") (pinfunction "PP_TP") (pintype "input"))
    )
    (net (code "39") (name "NC14") (class "Default")
      (node (ref "J1") (pin "57") (pinfunction "P$57_57") (pintype "bidirectional"))
      (node (ref "J3") (pin "41") (pinfunction "41_41") (pintype "bidirectional"))
      (node (ref "TP17") (pin "TP") (pinfunction "PP_TP") (pintype "input"))
    )
    (net (code "40") (name "NC15") (class "Default")
      (node (ref "J1") (pin "59") (pinfunction "P$59_59") (pintype "bidirectional"))
      (node (ref "J3") (pin "43") (pinfunction "43_43") (pintype "passive"))
      (node (ref "TP18") (pin "TP") (pinfunction "PP_TP") (pintype "input"))
    )
    (net (code "41") (name "NFC1") (class "Default")
      (node (ref "J1") (pin "17") (pinfunction "P$17_17") (pintype "bidirectional"))
      (node (ref "J3") (pin "11") (pinfunction "11_11") (pintype "passive"))
      (node (ref "NFC") (pin "2@1") (pinfunction "GND_2@1") (pintype "passive"))
      (node (ref "NFC") (pin "2@2") (pinfunction "GND_2@2") (pintype "passive"))
      (node (ref "R37") (pin "1") (pinfunction "1_1") (pintype "bidirectional"))
      (node (ref "TP1") (pin "TP") (pinfunction "PP_TP") (pintype "input"))
    )
    (net (code "42") (name "NFC2") (class "Default")
      (node (ref "J1") (pin "19") (pinfunction "P$19_19") (pintype "bidirectional"))
      (node (ref "J3") (pin "13") (pinfunction "13_13") (pintype "passive"))
      (node (ref "NFC") (pin "1") (pinfunction "1_1") (pintype "passive"))
      (node (ref "R38") (pin "2") (pinfunction "2_2") (pintype "bidirectional"))
      (node (ref "TP2") (pin "TP") (pinfunction "PP_TP") (pintype "input"))
    )
    (net (code "43") (name "Net-(C1-P$2)") (class "Default")
      (node (ref "C1") (pin "2") (pinfunction "P$2_2") (pintype "passive"))
      (node (ref "R32") (pin "1") (pinfunction "1_1") (pintype "passive"))
      (node (ref "RJ45") (pin "R4") (pinfunction "TCT_R4") (pintype "bidirectional"))
    )
    (net (code "44") (name "Net-(C11-P$2)") (class "Default")
      (node (ref "C11") (pin "2") (pinfunction "P$2_2") (pintype "passive"))
      (node (ref "R26") (pin "2") (pinfunction "2_2") (pintype "passive"))
      (node (ref "U1") (pin "30") (pinfunction "XI/CLKIN_30") (pintype "passive"))
      (node (ref "Y1") (pin "3") (pinfunction "2_3") (pintype "passive"))
    )
    (net (code "45") (name "Net-(C12-P$2)") (class "Default")
      (node (ref "C12") (pin "2") (pinfunction "P$2_2") (pintype "passive"))
      (node (ref "R50") (pin "2") (pinfunction "2_2") (pintype "bidirectional"))
      (node (ref "Y1") (pin "1") (pinfunction "1_1") (pintype "passive"))
    )
    (net (code "46") (name "Net-(C14-P$2)") (class "Default")
      (node (ref "C14") (pin "2") (pinfunction "P$2_2") (pintype "passive"))
      (node (ref "R40") (pin "1") (pinfunction "1_1") (pintype "passive"))
      (node (ref "R41") (pin "1") (pinfunction "1_1") (pintype "passive"))
      (node (ref "RJ45") (pin "R3") (pinfunction "RCT_R3") (pintype "bidirectional"))
    )
    (net (code "47") (name "Net-(C15-P$2)") (class "Default")
      (node (ref "C15") (pin "2") (pinfunction "P$2_2") (pintype "passive"))
      (node (ref "RJ45") (pin "R2") (pinfunction "RD+_R2") (pintype "bidirectional"))
    )
    (net (code "48") (name "Net-(C16-P$2)") (class "Default")
      (node (ref "C16") (pin "2") (pinfunction "P$2_2") (pintype "passive"))
      (node (ref "RJ45") (pin "R1") (pinfunction "RD-_R1") (pintype "bidirectional"))
    )
    (net (code "49") (name "Net-(C26-P$2)") (class "Default")
      (node (ref "C26") (pin "2") (pinfunction "P$2_2") (pintype "passive"))
      (node (ref "U1") (pin "22") (pinfunction "1V2O_22") (pintype "passive"))
    )
    (net (code "50") (name "Net-(D5-PadA)") (class "Default")
      (node (ref "D5") (pin "A") (pinfunction "A_A") (pintype "passive"))
      (node (ref "R44") (pin "1") (pinfunction "1_1") (pintype "passive"))
    )
    (net (code "51") (name "Net-(D7-PadANODE)") (class "Default")
      (node (ref "D7") (pin "ANODE") (pinfunction "ANODE_ANODE") (pintype "bidirectional"))
      (node (ref "J2") (pin "1") (pinfunction "1_1") (pintype "passive"))
    )
    (net (code "52") (name "Net-(D8-P$2)") (class "Default")
      (node (ref "D8") (pin "2") (pinfunction "P$2_2") (pintype "bidirectional"))
      (node (ref "DEBUG") (pin "1") (pinfunction "1_1") (pintype "bidirectional"))
      (node (ref "U$1") (pin "P$1") (pinfunction "TP_P$1") (pintype "bidirectional"))
    )
    (net (code "53") (name "Net-(F1-1)") (class "Default")
      (node (ref "D6") (pin "2") (pinfunction "2_2") (pintype "bidirectional"))
      (node (ref "F1") (pin "P$1") (pinfunction "1_P$1") (pintype "bidirectional"))
      (node (ref "USB1") (pin "1") (pinfunction "VBUS_1") (pintype "bidirectional"))
    )
    (net (code "54") (name "Net-(F2-1)") (class "Default")
      (node (ref "D1") (pin "2") (pinfunction "2_2") (pintype "bidirectional"))
      (node (ref "F2") (pin "P$1") (pinfunction "1_P$1") (pintype "bidirectional"))
      (node (ref "USB2") (pin "1") (pinfunction "VBUS_1") (pintype "bidirectional"))
    )
    (net (code "55") (name "Net-(J4-1)") (class "Default")
      (node (ref "J4") (pin "2") (pinfunction "1_2") (pintype "passive"))
      (node (ref "Q2") (pin "3") (pinfunction "3_3") (pintype "bidirectional"))
    )
    (net (code "56") (name "Net-(J7-Pad1)") (class "Default")
      (node (ref "J7") (pin "1") (pinfunction "1_1") (pintype "passive"))
      (node (ref "R44") (pin "2") (pinfunction "2_2") (pintype "passive"))
    )
    (net (code "57") (name "Net-(L2-1)") (class "Default")
      (node (ref "L2") (pin "P$1") (pinfunction "1_P$1") (pintype "passive"))
      (node (ref "U3") (pin "1") (pinfunction "LX_1") (pintype "bidirectional"))
    )
    (net (code "58") (name "Net-(LED1-A)") (class "Default")
      (node (ref "LED1") (pin "1") (pinfunction "A_1") (pintype "bidirectional"))
      (node (ref "R14") (pin "2") (pinfunction "2_2") (pintype "bidirectional"))
    )
    (net (code "59") (name "Net-(LED2-A)") (class "Default")
      (node (ref "LED2") (pin "1") (pinfunction "A_1") (pintype "bidirectional"))
      (node (ref "R52") (pin "2") (pinfunction "2_2") (pintype "bidirectional"))
    )
    (net (code "60") (name "Net-(Q2-Pad1)") (class "Default")
      (node (ref "Q2") (pin "1") (pinfunction "1_1") (pintype "bidirectional"))
      (node (ref "Q3") (pin "1") (pinfunction "1_1") (pintype "bidirectional"))
      (node (ref "R7") (pin "1") (pinfunction "1_1") (pintype "bidirectional"))
      (node (ref "R8") (pin "1") (pinfunction "1_1") (pintype "bidirectional"))
    )
    (net (code "61") (name "Net-(Q2-Pad2)") (class "Default")
      (node (ref "Q2") (pin "2") (pinfunction "2_2") (pintype "bidirectional"))
      (node (ref "Q3") (pin "2") (pinfunction "2_2") (pintype "bidirectional"))
      (node (ref "R7") (pin "2") (pinfunction "2_2") (pintype "bidirectional"))
    )
    (net (code "62") (name "Net-(R8-Pad2)") (class "Default")
      (node (ref "R8") (pin "2") (pinfunction "2_2") (pintype "bidirectional"))
      (node (ref "S4") (pin "3") (pinfunction "3_3") (pintype "bidirectional"))
      (node (ref "S4") (pin "6") (pinfunction "6_6") (pintype "bidirectional"))
    )
    (net (code "63") (name "Net-(R55-Pad1)") (class "Default")
      (node (ref "R55") (pin "1") (pinfunction "1_1") (pintype "passive"))
      (node (ref "S1") (pin "3") (pinfunction "3_3") (pintype "bidirectional"))
      (node (ref "S1") (pin "6") (pinfunction "6_6") (pintype "bidirectional"))
    )
    (net (code "64") (name "Net-(RGB-2)") (class "Default")
      (node (ref "R15") (pin "2") (pinfunction "2_2") (pintype "bidirectional"))
      (node (ref "RGB") (pin "BLUE") (pinfunction "2_BLUE") (pintype "passive"))
    )
    (net (code "65") (name "Net-(RGB-3)") (class "Default")
      (node (ref "R13") (pin "2") (pinfunction "2_2") (pintype "bidirectional"))
      (node (ref "RGB") (pin "GREEN") (pinfunction "3_GREEN") (pintype "passive"))
    )
    (net (code "66") (name "Net-(RGB-4)") (class "Default")
      (node (ref "R12") (pin "2") (pinfunction "2_2") (pintype "bidirectional"))
      (node (ref "RGB") (pin "RED") (pinfunction "4_RED") (pintype "passive"))
    )
    (net (code "67") (name "Net-(RJ45-L2Y-)") (class "Default")
      (node (ref "R48") (pin "1") (pinfunction "1_1") (pintype "passive"))
      (node (ref "RJ45") (pin "12") (pinfunction "L2Y-_12") (pintype "bidirectional"))
    )
    (net (code "68") (name "Net-(RJ45-L4G-)") (class "Default")
      (node (ref "R47") (pin "1") (pinfunction "1_1") (pintype "passive"))
      (node (ref "RJ45") (pin "14") (pinfunction "L4G-_14") (pintype "bidirectional"))
    )
    (net (code "69") (name "Net-(RN1A-2)") (class "Default")
      (node (ref "RN1") (pin "8") (pinfunction "2_8") (pintype "passive"))
      (node (ref "U1") (pin "38") (pinfunction "RSVD_38") (pintype "passive"))
    )
    (net (code "70") (name "Net-(RN1B-2)") (class "Default")
      (node (ref "RN1") (pin "7") (pinfunction "2_7") (pintype "passive"))
      (node (ref "U1") (pin "39") (pinfunction "RSVD_39") (pintype "passive"))
    )
    (net (code "71") (name "Net-(RN1C-2)") (class "Default")
      (node (ref "RN1") (pin "6") (pinfunction "2_6") (pintype "passive"))
      (node (ref "U1") (pin "40") (pinfunction "RSVD_40") (pintype "passive"))
    )
    (net (code "72") (name "Net-(RN1D-2)") (class "Default")
      (node (ref "RN1") (pin "5") (pinfunction "2_5") (pintype "passive"))
      (node (ref "U1") (pin "41") (pinfunction "RSVD_41") (pintype "passive"))
    )
    (net (code "73") (name "Net-(RN2A-2)") (class "Default")
      (node (ref "RN2") (pin "8") (pinfunction "2_8") (pintype "passive"))
      (node (ref "U1") (pin "42") (pinfunction "RSVD_42") (pintype "passive"))
    )
    (net (code "74") (name "Net-(RN2B-2)") (class "Default")
      (node (ref "RN2") (pin "7") (pinfunction "2_7") (pintype "passive"))
      (node (ref "U1") (pin "43") (pinfunction "PMODE2_43") (pintype "passive"))
    )
    (net (code "75") (name "Net-(RN2C-2)") (class "Default")
      (node (ref "RN2") (pin "6") (pinfunction "2_6") (pintype "passive"))
      (node (ref "U1") (pin "44") (pinfunction "PMODE1_44") (pintype "passive"))
    )
    (net (code "76") (name "Net-(RN2D-2)") (class "Default")
      (node (ref "RN2") (pin "5") (pinfunction "2_5") (pintype "passive"))
      (node (ref "U1") (pin "45") (pinfunction "PMODE0_45") (pintype "passive"))
    )
    (net (code "77") (name "Net-(U1-EXRES1)") (class "Default")
      (node (ref "R23") (pin "2") (pinfunction "2_2") (pintype "passive"))
      (node (ref "U1") (pin "10") (pinfunction "EXRES1_10") (pintype "passive"))
    )
    (net (code "78") (name "Net-(U1-MISO)") (class "Default")
      (node (ref "R51") (pin "1") (pinfunction "1_1") (pintype "passive"))
      (node (ref "R59") (pin "1") (pinfunction "1_1") (pintype "passive"))
      (node (ref "U1") (pin "34") (pinfunction "MISO_34") (pintype "passive"))
    )
    (net (code "79") (name "Net-(U1-MOSI)") (class "Default")
      (node (ref "R19") (pin "1") (pinfunction "1_1") (pintype "passive"))
      (node (ref "R60") (pin "1") (pinfunction "1_1") (pintype "passive"))
      (node (ref "U1") (pin "35") (pinfunction "MOSI_35") (pintype "passive"))
    )
    (net (code "80") (name "Net-(U1-RXN)") (class "Default")
      (node (ref "R46") (pin "2") (pinfunction "2_2") (pintype "passive"))
      (node (ref "U1") (pin "5") (pinfunction "RXN_5") (pintype "passive"))
    )
    (net (code "81") (name "Net-(U1-RXP)") (class "Default")
      (node (ref "R45") (pin "2") (pinfunction "2_2") (pintype "passive"))
      (node (ref "U1") (pin "6") (pinfunction "RXP_6") (pintype "passive"))
    )
    (net (code "82") (name "Net-(U1-SCLK)") (class "Default")
      (node (ref "R53") (pin "1") (pinfunction "1_1") (pintype "passive"))
      (node (ref "U1") (pin "33") (pinfunction "SCLK_33") (pintype "passive"))
    )
    (net (code "83") (name "Net-(U1-SCS_N)") (class "Default")
      (node (ref "R24") (pin "1") (pinfunction "1_1") (pintype "passive"))
      (node (ref "R57") (pin "1") (pinfunction "1_1") (pintype "passive"))
      (node (ref "U1") (pin "32") (pinfunction "SCS_N_32") (pintype "passive"))
    )
    (net (code "84") (name "Net-(U1-TOCAP)") (class "Default")
      (node (ref "C31") (pin "1") (pinfunction "1_1") (pintype "passive"))
      (node (ref "U1") (pin "20") (pinfunction "TOCAP_20") (pintype "passive"))
    )
    (net (code "85") (name "Net-(U1-TXN)") (class "Default")
      (node (ref "R43") (pin "2") (pinfunction "2_2") (pintype "passive"))
      (node (ref "U1") (pin "1") (pinfunction "TXN_1") (pintype "passive"))
    )
    (net (code "86") (name "Net-(U1-TXP)") (class "Default")
      (node (ref "R42") (pin "2") (pinfunction "2_2") (pintype "passive"))
      (node (ref "U1") (pin "2") (pinfunction "TXP_2") (pintype "passive"))
    )
    (net (code "87") (name "Net-(U1-XO)") (class "Default")
      (node (ref "R26") (pin "1") (pinfunction "1_1") (pintype "passive"))
      (node (ref "R50") (pin "1") (pinfunction "1_1") (pintype "bidirectional"))
      (node (ref "U1") (pin "31") (pinfunction "XO_31") (pintype "passive"))
    )
    (net (code "88") (name "Net-(U3-CE)") (class "Default")
      (node (ref "R11") (pin "2") (pinfunction "2_2") (pintype "passive"))
      (node (ref "U3") (pin "4") (pinfunction "CE_4") (pintype "bidirectional"))
    )
    (net (code "89") (name "Net-(U13-CELL)") (class "Default")
      (node (ref "C55") (pin "1") (pinfunction "1_1") (pintype "passive"))
      (node (ref "R54") (pin "2") (pinfunction "2_2") (pintype "passive"))
      (node (ref "U13") (pin "2") (pinfunction "CELL_2") (pintype "bidirectional"))
    )
    (net (code "90") (name "Net-(U13-VDD)") (class "Default")
      (node (ref "C54") (pin "1") (pinfunction "1_1") (pintype "passive"))
      (node (ref "R16") (pin "1") (pinfunction "1_1") (pintype "passive"))
      (node (ref "U13") (pin "3") (pinfunction "VDD_3") (pintype "bidirectional"))
    )
    (net (code "91") (name "Net-(USB1-D+)") (class "Default")
      (node (ref "R5") (pin "2") (pinfunction "2_2") (pintype "bidirectional"))
      (node (ref "USB1") (pin "3") (pinfunction "D+_3") (pintype "bidirectional"))
      (node (ref "Z1") (pin "2") (pinfunction "2_2") (pintype "passive"))
    )
    (net (code "92") (name "Net-(USB1-D-)") (class "Default")
      (node (ref "R6") (pin "2") (pinfunction "2_2") (pintype "bidirectional"))
      (node (ref "USB1") (pin "2") (pinfunction "D-_2") (pintype "bidirectional"))
      (node (ref "Z2") (pin "2") (pinfunction "2_2") (pintype "passive"))
    )
    (net (code "93") (name "Net-(USB1-ID)") (class "Default")
      (node (ref "R20") (pin "1") (pinfunction "1_1") (pintype "bidirectional"))
      (node (ref "R21") (pin "1") (pinfunction "1_1") (pintype "bidirectional"))
      (node (ref "R22") (pin "1") (pinfunction "1_1") (pintype "bidirectional"))
      (node (ref "USB1") (pin "4") (pinfunction "ID_4") (pintype "bidirectional"))
    )
    (net (code "94") (name "OTG") (class "Default")
      (node (ref "R3") (pin "2") (pinfunction "2_2") (pintype "passive"))
      (node (ref "U14") (pin "8") (pinfunction "OTG_8") (pintype "bidirectional"))
    )
    (net (code "95") (name "PMIC_SYS") (class "Default")
      (node (ref "C47") (pin "1") (pinfunction "1_1") (pintype "passive"))
      (node (ref "C58") (pin "1") (pinfunction "1_1") (pintype "passive"))
      (node (ref "C59") (pin "1") (pinfunction "1_1") (pintype "passive"))
      (node (ref "J7") (pin "2") (pinfunction "2_2") (pintype "passive"))
      (node (ref "L7") (pin "P$2") (pinfunction "2_P$2") (pintype "passive"))
      (node (ref "R4") (pin "2") (pinfunction "2_2") (pintype "bidirectional"))
      (node (ref "U14") (pin "15") (pinfunction "SYS_15") (pintype "power_in"))
      (node (ref "U14") (pin "16") (pinfunction "SYS_16") (pintype "power_in"))
      (node (ref "U2") (pin "5") (pinfunction "VIN_5") (pintype "power_in"))
    )
    (net (code "96") (name "PMID") (class "Default")
      (node (ref "C56") (pin "1") (pinfunction "1_1") (pintype "passive"))
      (node (ref "C62") (pin "1") (pinfunction "1_1") (pintype "passive"))
      (node (ref "U14") (pin "23") (pinfunction "PMID_23") (pintype "passive"))
    )
    (net (code "97") (name "PWM0") (class "Default")
      (node (ref "J1") (pin "66") (pinfunction "P$66_66") (pintype "bidirectional"))
      (node (ref "J12") (pin "1") (pinfunction "1_1") (pintype "passive"))
      (node (ref "J3") (pin "52") (pinfunction "52_52") (pintype "passive"))
      (node (ref "TP47") (pin "TP") (pinfunction "PP_TP") (pintype "input"))
    )
    (net (code "98") (name "PWM1") (class "Default")
      (node (ref "J1") (pin "68") (pinfunction "P$68_68") (pintype "bidirectional"))
      (node (ref "J12") (pin "7") (pinfunction "7_7") (pintype "passive"))
      (node (ref "J3") (pin "54") (pinfunction "54_54") (pintype "passive"))
      (node (ref "TP48") (pin "TP") (pinfunction "PP_TP") (pintype "input"))
    )
    (net (code "99") (name "PWM2") (class "Default")
      (node (ref "J1") (pin "70") (pinfunction "P$70_70") (pintype "bidirectional"))
      (node (ref "J12") (pin "9") (pinfunction "9_9") (pintype "passive"))
      (node (ref "J3") (pin "56") (pinfunction "56_56") (pintype "passive"))
      (node (ref "TP49") (pin "TP") (pinfunction "PP_TP") (pintype "input"))
    )
    (net (code "100") (name "PWM3") (class "Default")
      (node (ref "J1") (pin "72") (pinfunction "P$72_72") (pintype "bidirectional"))
      (node (ref "J12") (pin "11") (pinfunction "11_11") (pintype "passive"))
      (node (ref "J3") (pin "58") (pinfunction "58_58") (pintype "passive"))
      (node (ref "TP50") (pin "TP") (pinfunction "PP_TP") (pintype "input"))
    )
    (net (code "101") (name "RED") (class "Default")
      (node (ref "J1") (pin "61") (pinfunction "P$61_61") (pintype "bidirectional"))
      (node (ref "J3") (pin "45") (pinfunction "45_45") (pintype "passive"))
      (node (ref "R12") (pin "1") (pinfunction "1_1") (pintype "bidirectional"))
      (node (ref "TP19") (pin "TP") (pinfunction "PP_TP") (pintype "input"))
    )
    (net (code "102") (name "REGN") (class "Default")
      (node (ref "C65") (pin "1") (pinfunction "1_1") (pintype "passive"))
      (node (ref "R35") (pin "1") (pinfunction "1_1") (pintype "passive"))
      (node (ref "U14") (pin "22") (pinfunction "REGN_22") (pintype "bidirectional"))
    )
    (net (code "103") (name "RTS") (class "Default")
      (node (ref "J1") (pin "42") (pinfunction "P$42_42") (pintype "bidirectional"))
      (node (ref "J12") (pin "3") (pinfunction "3_3") (pintype "passive"))
      (node (ref "J3") (pin "28") (pinfunction "28_28") (pintype "passive"))
      (node (ref "TP37") (pin "TP") (pinfunction "PP_TP") (pintype "input"))
    )
    (net (code "104") (name "RX") (class "Default")
      (node (ref "J1") (pin "38") (pinfunction "P$38_38") (pintype "bidirectional"))
      (node (ref "J3") (pin "24") (pinfunction "24_24") (pintype "passive"))
      (node (ref "TP35") (pin "TP") (pinfunction "PP_TP") (pintype "input"))
    )
    (net (code "105") (name "RX_N") (class "Default")
      (node (ref "C16") (pin "1") (pinfunction "P$1_1") (pintype "passive"))
      (node (ref "R41") (pin "2") (pinfunction "2_2") (pintype "passive"))
      (node (ref "R46") (pin "1") (pinfunction "1_1") (pintype "passive"))
    )
    (net (code "106") (name "RX_P") (class "Default")
      (node (ref "C15") (pin "1") (pinfunction "P$1_1") (pintype "passive"))
      (node (ref "R40") (pin "2") (pinfunction "2_2") (pintype "passive"))
      (node (ref "R45") (pin "1") (pinfunction "1_1") (pintype "passive"))
    )
    (net (code "107") (name "SCK") (class "Default")
      (node (ref "J1") (pin "54") (pinfunction "P$54_54") (pintype "bidirectional"))
      (node (ref "J3") (pin "40") (pinfunction "40_40") (pintype "passive"))
      (node (ref "J35") (pin "10") (pinfunction "10_10") (pintype "passive"))
      (node (ref "TP41") (pin "TP") (pinfunction "PP_TP") (pintype "input"))
    )
    (net (code "108") (name "SCL") (class "Default")
      (node (ref "J1") (pin "20") (pinfunction "P$20_20") (pintype "bidirectional"))
      (node (ref "J10") (pin "1") (pinfunction "1_1") (pintype "bidirectional"))
      (node (ref "J3") (pin "14") (pinfunction "14_14") (pintype "passive"))
      (node (ref "J35") (pin "22") (pinfunction "22_22") (pintype "passive"))
      (node (ref "TP30") (pin "TP") (pinfunction "PP_TP") (pintype "input"))
    )
    (net (code "109") (name "SCL-P") (class "Default")
      (node (ref "J35") (pin "21") (pinfunction "21_21") (pintype "passive"))
      (node (ref "R30") (pin "2") (pinfunction "2_2") (pintype "passive"))
      (node (ref "U13") (pin "7") (pinfunction "SCL_7") (pintype "bidirectional"))
      (node (ref "U14") (pin "5") (pinfunction "SCL_5") (pintype "output"))
    )
    (net (code "110") (name "SDA") (class "Default")
      (node (ref "J1") (pin "22") (pinfunction "P$22_22") (pintype "bidirectional"))
      (node (ref "J10") (pin "2") (pinfunction "2_2") (pintype "bidirectional"))
      (node (ref "J3") (pin "16") (pinfunction "16_16") (pintype "passive"))
      (node (ref "J35") (pin "20") (pinfunction "20_20") (pintype "passive"))
      (node (ref "TP31") (pin "TP") (pinfunction "PP_TP") (pintype "input"))
    )
    (net (code "111") (name "SDA-P") (class "Default")
      (node (ref "J35") (pin "19") (pinfunction "19_19") (pintype "passive"))
      (node (ref "R36") (pin "2") (pinfunction "2_2") (pintype "passive"))
      (node (ref "U13") (pin "8") (pinfunction "SDA_8") (pintype "bidirectional"))
      (node (ref "U14") (pin "6") (pinfunction "SDA_6") (pintype "bidirectional"))
    )
    (net (code "112") (name "SD_CLK1") (class "Default")
      (node (ref "J12") (pin "4") (pinfunction "4_4") (pintype "passive"))
      (node (ref "R27") (pin "2") (pinfunction "2_2") (pintype "bidirectional"))
      (node (ref "X4") (pin "5") (pinfunction "5-CLK_5") (pintype "bidirectional"))
    )
    (net (code "113") (name "SD_CS1") (class "Default")
      (node (ref "J12") (pin "8") (pinfunction "8_8") (pintype "passive"))
      (node (ref "R28") (pin "2") (pinfunction "2_2") (pintype "bidirectional"))
      (node (ref "X4") (pin "2") (pinfunction "2-CD/DAT3_2") (pintype "bidirectional"))
    )
    (net (code "114") (name "SD_DECT") (class "Default")
      (node (ref "J12") (pin "10") (pinfunction "10_10") (pintype "passive"))
      (node (ref "R9") (pin "1") (pinfunction "1_1") (pintype "bidirectional"))
      (node (ref "X4") (pin "GND3") (pinfunction "GND2_GND3") (pintype "power_in"))
      (node (ref "X4") (pin "GND4") (pinfunction "GND3_GND4") (pintype "power_in"))
    )
    (net (code "115") (name "SD_MISO1") (class "Default")
      (node (ref "J12") (pin "2") (pinfunction "2_2") (pintype "passive"))
      (node (ref "X4") (pin "7") (pinfunction "7-DAT0_7") (pintype "bidirectional"))
    )
    (net (code "116") (name "SD_MOSI1") (class "Default")
      (node (ref "J12") (pin "6") (pinfunction "6_6") (pintype "passive"))
      (node (ref "R29") (pin "2") (pinfunction "2_2") (pintype "bidirectional"))
      (node (ref "X4") (pin "3") (pinfunction "3-CMO_3") (pintype "bidirectional"))
    )
    (net (code "117") (name "SOM5") (class "Default")
      (node (ref "J1") (pin "67") (pinfunction "P$67_67") (pintype "bidirectional"))
      (node (ref "J3") (pin "51") (pinfunction "51_51") (pintype "passive"))
      (node (ref "TP22") (pin "TP") (pinfunction "PP_TP") (pintype "input"))
    )
    (net (code "118") (name "SOM6") (class "Default")
      (node (ref "J1") (pin "69") (pinfunction "P$69_69") (pintype "bidirectional"))
      (node (ref "J3") (pin "53") (pinfunction "53_53") (pintype "passive"))
      (node (ref "TP23") (pin "TP") (pinfunction "PP_TP") (pintype "input"))
    )
    (net (code "119") (name "SOM7") (class "Default")
      (node (ref "J1") (pin "71") (pinfunction "P$71_71") (pintype "bidirectional"))
      (node (ref "J3") (pin "55") (pinfunction "55_55") (pintype "passive"))
      (node (ref "TP24") (pin "TP") (pinfunction "PP_TP") (pintype "input"))
    )
    (net (code "120") (name "SOM8") (class "Default")
      (node (ref "J1") (pin "73") (pinfunction "P$73_73") (pintype "bidirectional"))
      (node (ref "J3") (pin "57") (pinfunction "57_57") (pintype "passive"))
      (node (ref "TP25") (pin "TP") (pinfunction "PP_TP") (pintype "input"))
    )
    (net (code "121") (name "SOM9") (class "Default")
      (node (ref "J1") (pin "75") (pinfunction "P$75_75") (pintype "bidirectional"))
      (node (ref "J3") (pin "59") (pinfunction "59_59") (pintype "passive"))
      (node (ref "TP26") (pin "TP") (pinfunction "PP_TP") (pintype "input"))
    )
    (net (code "122") (name "STAT") (class "Default")
      (node (ref "D5") (pin "C") (pinfunction "C_C") (pintype "passive"))
      (node (ref "U14") (pin "4") (pinfunction "STAT_4") (pintype "bidirectional"))
    )
    (net (code "123") (name "SW1") (class "Default")
      (node (ref "C17") (pin "2") (pinfunction "2_2") (pintype "passive"))
      (node (ref "L7") (pin "P$1") (pinfunction "1_P$1") (pintype "passive"))
      (node (ref "U14") (pin "19") (pinfunction "SW_19") (pintype "power_in"))
      (node (ref "U14") (pin "20") (pinfunction "SW_20") (pintype "power_in"))
    )
    (net (code "124") (name "SWDCLK") (class "Default")
      (node (ref "DEBUG") (pin "4") (pinfunction "4_4") (pintype "bidirectional"))
      (node (ref "P2") (pin "P$2") (pinfunction "TP_P$2") (pintype "bidirectional"))
      (node (ref "U$10") (pin "P$1") (pinfunction "TP_P$1") (pintype "bidirectional"))
    )
    (net (code "125") (name "SWDIO") (class "Default")
      (node (ref "DEBUG") (pin "2") (pinfunction "2_2") (pintype "bidirectional"))
      (node (ref "P1") (pin "P$2") (pinfunction "TP_P$2") (pintype "bidirectional"))
      (node (ref "U$9") (pin "P$1") (pinfunction "TP_P$1") (pintype "bidirectional"))
    )
    (net (code "126") (name "SWO") (class "Default")
      (node (ref "DEBUG") (pin "6") (pinfunction "6_6") (pintype "bidirectional"))
      (node (ref "P3") (pin "P$2") (pinfunction "TP_P$2") (pintype "bidirectional"))
      (node (ref "U$11") (pin "P$1") (pinfunction "TP_P$1") (pintype "bidirectional"))
    )
    (net (code "127") (name "SYS_PWR_EN") (class "Default")
      (node (ref "R4") (pin "1") (pinfunction "1_1") (pintype "bidirectional"))
      (node (ref "S1") (pin "2") (pinfunction "2_2") (pintype "bidirectional"))
      (node (ref "S1") (pin "5") (pinfunction "5_5") (pintype "bidirectional"))
      (node (ref "U2") (pin "4") (pinfunction "CE_4") (pintype "bidirectional"))
    )
    (net (code "128") (name "TS") (class "Default")
      (node (ref "R34") (pin "1") (pinfunction "1_1") (pintype "passive"))
      (node (ref "R35") (pin "2") (pinfunction "2_2") (pintype "passive"))
      (node (ref "U14") (pin "11") (pinfunction "TS_11") (pintype "bidirectional"))
      (node (ref "U14") (pin "12") (pinfunction "~{QON}_12") (pintype "bidirectional"))
    )
    (net (code "129") (name "TX") (class "Default")
      (node (ref "J1") (pin "36") (pinfunction "P$36_36") (pintype "bidirectional"))
      (node (ref "J3") (pin "22") (pinfunction "22_22") (pintype "passive"))
      (node (ref "TP34") (pin "TP") (pinfunction "PP_TP") (pintype "input"))
    )
    (net (code "130") (name "TX_N") (class "Default")
      (node (ref "R31") (pin "1") (pinfunction "1_1") (pintype "passive"))
      (node (ref "R43") (pin "1") (pinfunction "1_1") (pintype "passive"))
      (node (ref "RJ45") (pin "R5") (pinfunction "TD-_R5") (pintype "bidirectional"))
    )
    (net (code "131") (name "TX_P") (class "Default")
      (node (ref "R39") (pin "1") (pinfunction "1_1") (pintype "passive"))
      (node (ref "R42") (pin "1") (pinfunction "1_1") (pintype "passive"))
      (node (ref "RJ45") (pin "R6") (pinfunction "TD+_R6") (pintype "bidirectional"))
    )
    (net (code "132") (name "U-VBUS") (class "Default")
      (node (ref "F2") (pin "P$2") (pinfunction "2_P$2") (pintype "bidirectional"))
      (node (ref "J35") (pin "5") (pinfunction "5_5") (pintype "passive"))
    )
    (net (code "133") (name "UB_N") (class "Default")
      (node (ref "J1") (pin "46") (pinfunction "P$46_46") (pintype "bidirectional"))
      (node (ref "R18") (pin "2") (pinfunction "2_2") (pintype "bidirectional"))
    )
    (net (code "134") (name "UB_P") (class "Default")
      (node (ref "J1") (pin "44") (pinfunction "P$44_44") (pintype "bidirectional"))
      (node (ref "R17") (pin "2") (pinfunction "2_2") (pintype "bidirectional"))
    )
    (net (code "135") (name "UB_USB_N") (class "Default")
      (node (ref "J35") (pin "2") (pinfunction "2_2") (pintype "passive"))
      (node (ref "R18") (pin "1") (pinfunction "1_1") (pintype "bidirectional"))
    )
    (net (code "136") (name "UB_USB_P") (class "Default")
      (node (ref "J35") (pin "4") (pinfunction "4_4") (pintype "passive"))
      (node (ref "R17") (pin "1") (pinfunction "1_1") (pintype "bidirectional"))
    )
    (net (code "137") (name "USBD_N") (class "Default")
      (node (ref "J1") (pin "13") (pinfunction "P$13_13") (pintype "bidirectional"))
      (node (ref "R6") (pin "1") (pinfunction "1_1") (pintype "bidirectional"))
      (node (ref "U14") (pin "3") (pinfunction "~{PG}_3") (pintype "output"))
    )
    (net (code "138") (name "USBD_P") (class "Default")
      (node (ref "J1") (pin "11") (pinfunction "P$11_11") (pintype "bidirectional"))
      (node (ref "R5") (pin "1") (pinfunction "1_1") (pintype "bidirectional"))
      (node (ref "U14") (pin "2") (pinfunction "PSEL_2") (pintype "output"))
    )
    (net (code "139") (name "USBID") (class "Default")
      (node (ref "R21") (pin "2") (pinfunction "2_2") (pintype "bidirectional"))
    )
    (net (code "140") (name "USB_DET") (class "Default")
      (node (ref "J1") (pin "74") (pinfunction "P$74_74") (pintype "bidirectional"))
      (node (ref "J35") (pin "6") (pinfunction "6_6") (pintype "passive"))
    )
    (net (code "141") (name "USER_D7") (class "Default")
      (node (ref "J12") (pin "12") (pinfunction "12_12") (pintype "passive"))
      (node (ref "R52") (pin "1") (pinfunction "1_1") (pintype "bidirectional"))
    )
    (net (code "142") (name "UVCC") (class "Default")
      (node (ref "J1") (pin "2") (pinfunction "P$2_2") (pintype "bidirectional"))
      (node (ref "J1") (pin "4") (pinfunction "P$4_4") (pintype "bidirectional"))
      (node (ref "J1") (pin "6") (pinfunction "P$6_6") (pintype "bidirectional"))
      (node (ref "J1") (pin "8") (pinfunction "P$8_8") (pintype "bidirectional"))
      (node (ref "J5") (pin "1") (pinfunction "1_1") (pintype "passive"))
    )
    (net (code "143") (name "U_N") (class "Default")
      (node (ref "J35") (pin "1") (pinfunction "1_1") (pintype "passive"))
      (node (ref "USB2") (pin "2") (pinfunction "D-_2") (pintype "bidirectional"))
      (node (ref "Z6") (pin "2") (pinfunction "2_2") (pintype "passive"))
    )
    (net (code "144") (name "U_P") (class "Default")
      (node (ref "J35") (pin "3") (pinfunction "3_3") (pintype "passive"))
      (node (ref "USB2") (pin "3") (pinfunction "D+_3") (pintype "bidirectional"))
      (node (ref "Z5") (pin "2") (pinfunction "2_2") (pintype "passive"))
    )
    (net (code "145") (name "V+") (class "Default")
      (node (ref "J16") (pin "2") (pinfunction "2_2") (pintype "passive"))
      (node (ref "RJ45") (pin "R9") (pinfunction "V+_R9") (pintype "bidirectional"))
    )
    (net (code "146") (name "V-") (class "Default")
      (node (ref "J16") (pin "1") (pinfunction "1_1") (pintype "passive"))
      (node (ref "RJ45") (pin "R10") (pinfunction "V-_R10") (pintype "bidirectional"))
    )
    (net (code "147") (name "VBAT") (class "Default")
      (node (ref "C63") (pin "1") (pinfunction "1_1") (pintype "passive"))
      (node (ref "Q3") (pin "3") (pinfunction "3_3") (pintype "bidirectional"))
      (node (ref "R54") (pin "1") (pinfunction "1_1") (pintype "passive"))
      (node (ref "U14") (pin "13") (pinfunction "BAT_13") (pintype "passive"))
      (node (ref "U14") (pin "14") (pinfunction "BAT_14") (pintype "power_in"))
    )
    (net (code "148") (name "VCC") (class "Default")
      (node (ref "C4") (pin "1") (pinfunction "1_1") (pintype "passive"))
      (node (ref "C6") (pin "2") (pinfunction "P$2_2") (pintype "passive"))
      (node (ref "J3") (pin "2") (pinfunction "2_2") (pintype "passive"))
      (node (ref "J3") (pin "4") (pinfunction "4_4") (pintype "passive"))
      (node (ref "J3") (pin "6") (pinfunction "6_6") (pintype "passive"))
      (node (ref "J5") (pin "2") (pinfunction "2_2") (pintype "passive"))
      (node (ref "R11") (pin "1") (pinfunction "1_1") (pintype "passive"))
      (node (ref "TP51") (pin "TP") (pinfunction "PP_TP") (pintype "input"))
      (node (ref "U2") (pin "1") (pinfunction "VOUT_1") (pintype "power_in"))
      (node (ref "U3") (pin "6") (pinfunction "VIN_6") (pintype "power_in"))
    )
    (net (code "149") (name "VIN") (class "Default")
      (node (ref "C57") (pin "1") (pinfunction "1_1") (pintype "passive"))
      (node (ref "C60") (pin "1") (pinfunction "1_1") (pintype "passive"))
      (node (ref "C64") (pin "1") (pinfunction "1_1") (pintype "passive"))
      (node (ref "D3") (pin "CATHODE") (pinfunction "CATHODE_CATHODE") (pintype "bidirectional"))
      (node (ref "D4") (pin "CATHODE") (pinfunction "CATHODE_CATHODE") (pintype "bidirectional"))
      (node (ref "D7") (pin "CATHODE") (pinfunction "CATHODE_CATHODE") (pintype "bidirectional"))
      (node (ref "U14") (pin "1") (pinfunction "VBUS_1") (pintype "power_in"))
      (node (ref "U14") (pin "24") (pinfunction "VBUS_24") (pintype "passive"))
    )
    (net (code "150") (name "VPOE") (class "Default")
      (node (ref "D3") (pin "ANODE") (pinfunction "ANODE_ANODE") (pintype "bidirectional"))
      (node (ref "J14") (pin "1") (pinfunction "1_1") (pintype "passive"))
    )
    (net (code "151") (name "VREG_1P8") (class "Default")
      (node (ref "R22") (pin "2") (pinfunction "2_2") (pintype "bidirectional"))
      (node (ref "TP3") (pin "P$1") (pinfunction "1_P$1") (pintype "bidirectional"))
    )
    (net (code "152") (name "VUSB") (class "Default")
      (node (ref "F1") (pin "P$2") (pinfunction "2_P$2") (pintype "bidirectional"))
      (node (ref "R61") (pin "1") (pinfunction "1_1") (pintype "passive"))
    )
    (net (code "153") (name "VUSB1") (class "Default")
      (node (ref "D4") (pin "ANODE") (pinfunction "ANODE_ANODE") (pintype "bidirectional"))
      (node (ref "J1") (pin "16") (pinfunction "P$16_16") (pintype "bidirectional"))
      (node (ref "R61") (pin "2") (pinfunction "2_2") (pintype "passive"))
    )
    (net (code "154") (name "unconnected-(DEBUG-Pad7)") (class "Default")
      (node (ref "DEBUG") (pin "7") (pinfunction "7_7") (pintype "bidirectional"))
    )
    (net (code "155") (name "unconnected-(DEBUG-Pad8)") (class "Default")
      (node (ref "DEBUG") (pin "8") (pinfunction "8_8") (pintype "bidirectional"))
    )
    (net (code "156") (name "unconnected-(J3-Pad30)") (class "Default")
      (node (ref "J3") (pin "30") (pinfunction "30_30") (pintype "passive"))
    )
    (net (code "157") (name "unconnected-(J3-Pad32)") (class "Default")
      (node (ref "J3") (pin "32") (pinfunction "32_32") (pintype "passive"))
    )
    (net (code "158") (name "unconnected-(J3-Pad60)") (class "Default")
      (node (ref "J3") (pin "60") (pinfunction "60_60") (pintype "passive"))
    )
    (net (code "159") (name "unconnected-(RJ45-NC-PadR7)") (class "Default")
      (node (ref "RJ45") (pin "R7") (pinfunction "NC_R7") (pintype "bidirectional"))
    )
    (net (code "160") (name "unconnected-(RJ45-NC-PadR8)") (class "Default")
      (node (ref "RJ45") (pin "R8") (pinfunction "NC_R8") (pintype "bidirectional"))
    )
    (net (code "161") (name "unconnected-(S1-Pad1)") (class "Default")
      (node (ref "S1") (pin "1") (pinfunction "1_1") (pintype "bidirectional"))
    )
    (net (code "162") (name "unconnected-(S1-Pad4)") (class "Default")
      (node (ref "S1") (pin "4") (pinfunction "4_4") (pintype "bidirectional"))
    )
    (net (code "163") (name "unconnected-(S4-Pad1)") (class "Default")
      (node (ref "S4") (pin "1") (pinfunction "1_1") (pintype "bidirectional"))
    )
    (net (code "164") (name "unconnected-(S4-Pad4)") (class "Default")
      (node (ref "S4") (pin "4") (pinfunction "4_4") (pintype "bidirectional"))
    )
    (net (code "165") (name "unconnected-(U1-DNC-Pad7)") (class "Default")
      (node (ref "U1") (pin "7") (pinfunction "DNC_7") (pintype "passive"))
    )
    (net (code "166") (name "unconnected-(U1-DUPLED-Pad26)") (class "Default")
      (node (ref "U1") (pin "26") (pinfunction "DUPLED_26") (pintype "passive"))
    )
    (net (code "167") (name "unconnected-(U1-NC-Pad12)") (class "Default")
      (node (ref "U1") (pin "12") (pinfunction "NC_12") (pintype "passive"))
    )
    (net (code "168") (name "unconnected-(U1-NC-Pad13)") (class "Default")
      (node (ref "U1") (pin "13") (pinfunction "NC_13") (pintype "passive"))
    )
    (net (code "169") (name "unconnected-(U1-NC-Pad46)") (class "Default")
      (node (ref "U1") (pin "46") (pinfunction "NC_46") (pintype "passive"))
    )
    (net (code "170") (name "unconnected-(U1-NC-Pad47)") (class "Default")
      (node (ref "U1") (pin "47") (pinfunction "NC_47") (pintype "passive"))
    )
    (net (code "171") (name "unconnected-(U1-SPDLED-Pad24)") (class "Default")
      (node (ref "U1") (pin "24") (pinfunction "SPDLED_24") (pintype "passive"))
    )
    (net (code "172") (name "unconnected-(U1-VBG-Pad18)") (class "Default")
      (node (ref "U1") (pin "18") (pinfunction "VBG_18") (pintype "passive"))
    )
    (net (code "173") (name "unconnected-(U2-FLG-Pad3)") (class "Default")
      (node (ref "U2") (pin "3") (pinfunction "FLG_3") (pintype "bidirectional"))
    )
    (net (code "174") (name "unconnected-(X1-Pad1)") (class "Default")
      (node (ref "X1") (pin "1") (pinfunction "1_1") (pintype "passive"))
    )
    (net (code "175") (name "unconnected-(X3-Pad1)") (class "Default")
      (node (ref "X3") (pin "1") (pinfunction "1_1") (pintype "passive"))
    )
    (net (code "176") (name "unconnected-(X4-1-DAT2-Pad1)") (class "Default")
      (node (ref "X4") (pin "1") (pinfunction "1-DAT2_1") (pintype "bidirectional"))
    )
    (net (code "177") (name "unconnected-(X4-8-DAT1-Pad8)") (class "Default")
      (node (ref "X4") (pin "8") (pinfunction "8-DAT1_8") (pintype "bidirectional"))
    )
    (net (code "178") (name "{slash}RESET") (class "Default")
      (node (ref "C24") (pin "2") (pinfunction "P$2_2") (pintype "passive"))
      (node (ref "J1") (pin "34") (pinfunction "P$34_34") (pintype "bidirectional"))
      (node (ref "J3") (pin "20") (pinfunction "20_20") (pintype "passive"))
      (node (ref "R1") (pin "1") (pinfunction "1_1") (pintype "bidirectional"))
      (node (ref "RESET") (pin "3") (pinfunction "P$3_3") (pintype "bidirectional"))
      (node (ref "RESET") (pin "4") (pinfunction "P$4_4") (pintype "bidirectional"))
      (node (ref "TP33") (pin "TP") (pinfunction "PP_TP") (pintype "input"))
      (node (ref "Z4") (pin "2") (pinfunction "2_2") (pintype "passive"))
    )
    (net (code "179") (name "{slash}REST") (class "Default")
      (node (ref "DEBUG") (pin "10") (pinfunction "10_10") (pintype "bidirectional"))
      (node (ref "P4") (pin "P$2") (pinfunction "TP_P$2") (pintype "bidirectional"))
      (node (ref "U$12") (pin "P$1") (pinfunction "TP_P$1") (pintype "bidirectional"))
    )
    (net (code "180") (name "~{CE}") (class "Default")
      (node (ref "R10") (pin "2") (pinfunction "2_2") (pintype "passive"))
      (node (ref "U14") (pin "9") (pinfunction "~{CE}_9") (pintype "output"))
    )
    (net (code "181") (name "~{ETH_INT}") (class "Default")
      (node (ref "J35") (pin "15") (pinfunction "15_15") (pintype "passive"))
      (node (ref "R25") (pin "1") (pinfunction "1_1") (pintype "passive"))
      (node (ref "U1") (pin "36") (pinfunction "INT_N_36") (pintype "passive"))
    )
    (net (code "182") (name "~{FUEL-INT}") (class "Default")
      (node (ref "J35") (pin "17") (pinfunction "17_17") (pintype "passive"))
      (node (ref "R2") (pin "2") (pinfunction "2_2") (pintype "passive"))
      (node (ref "U13") (pin "5") (pinfunction "ALT_5") (pintype "bidirectional"))
      (node (ref "U14") (pin "7") (pinfunction "INT_7") (pintype "bidirectional"))
    )
    (net (code "183") (name "~{RESET}") (class "Default")
      (node (ref "C30") (pin "2") (pinfunction "P$2_2") (pintype "passive"))
      (node (ref "R49") (pin "1") (pinfunction "1_1") (pintype "passive"))
      (node (ref "R56") (pin "1") (pinfunction "1_1") (pintype "passive"))
      (node (ref "U1") (pin "37") (pinfunction "RST_N_37") (pintype "passive"))
    )
  )
)
